# node.net
KiCad netlist of a schematic drawn in EAGLE
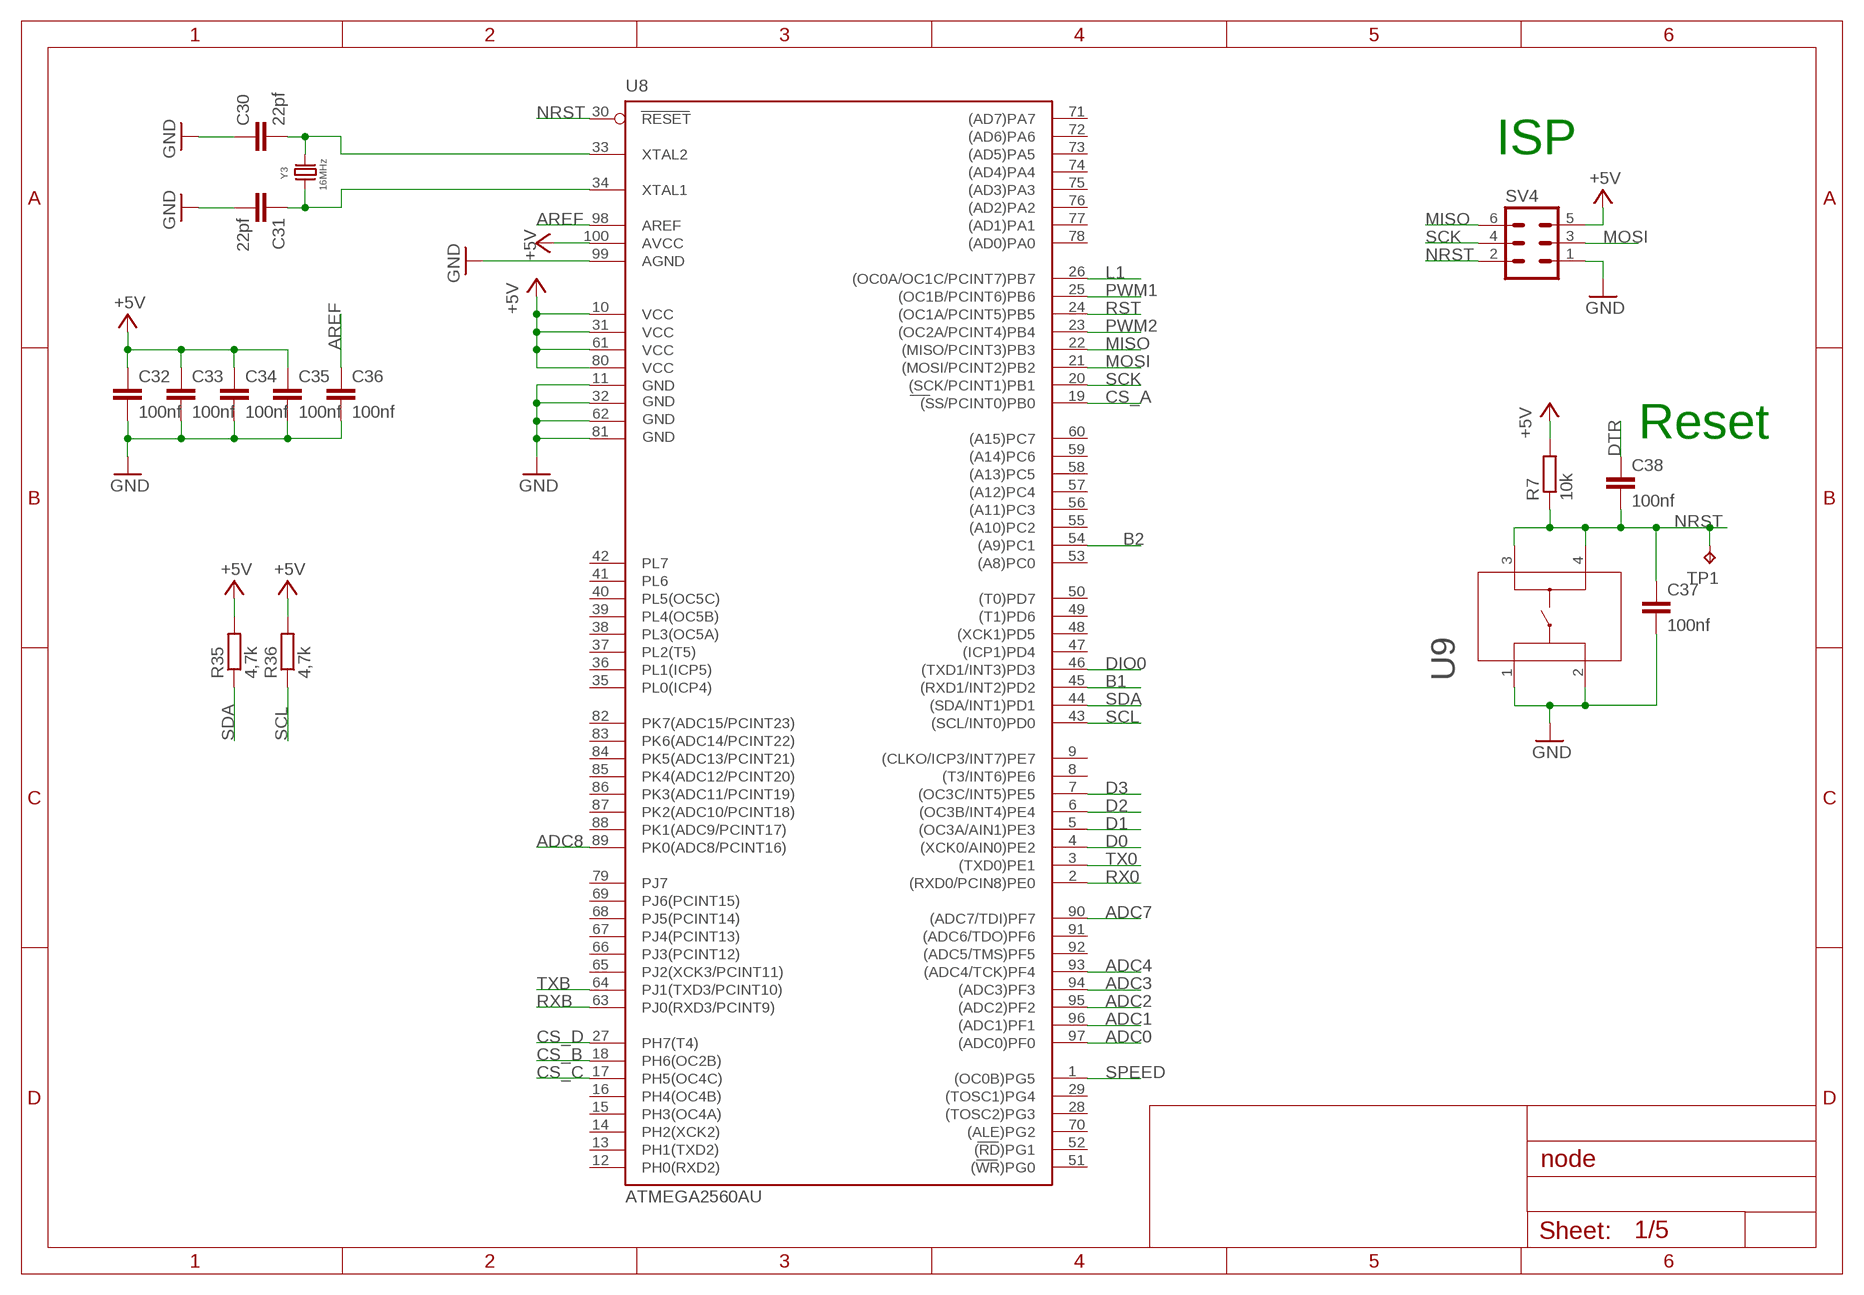
[diagram p0: schematic, sheet 1]
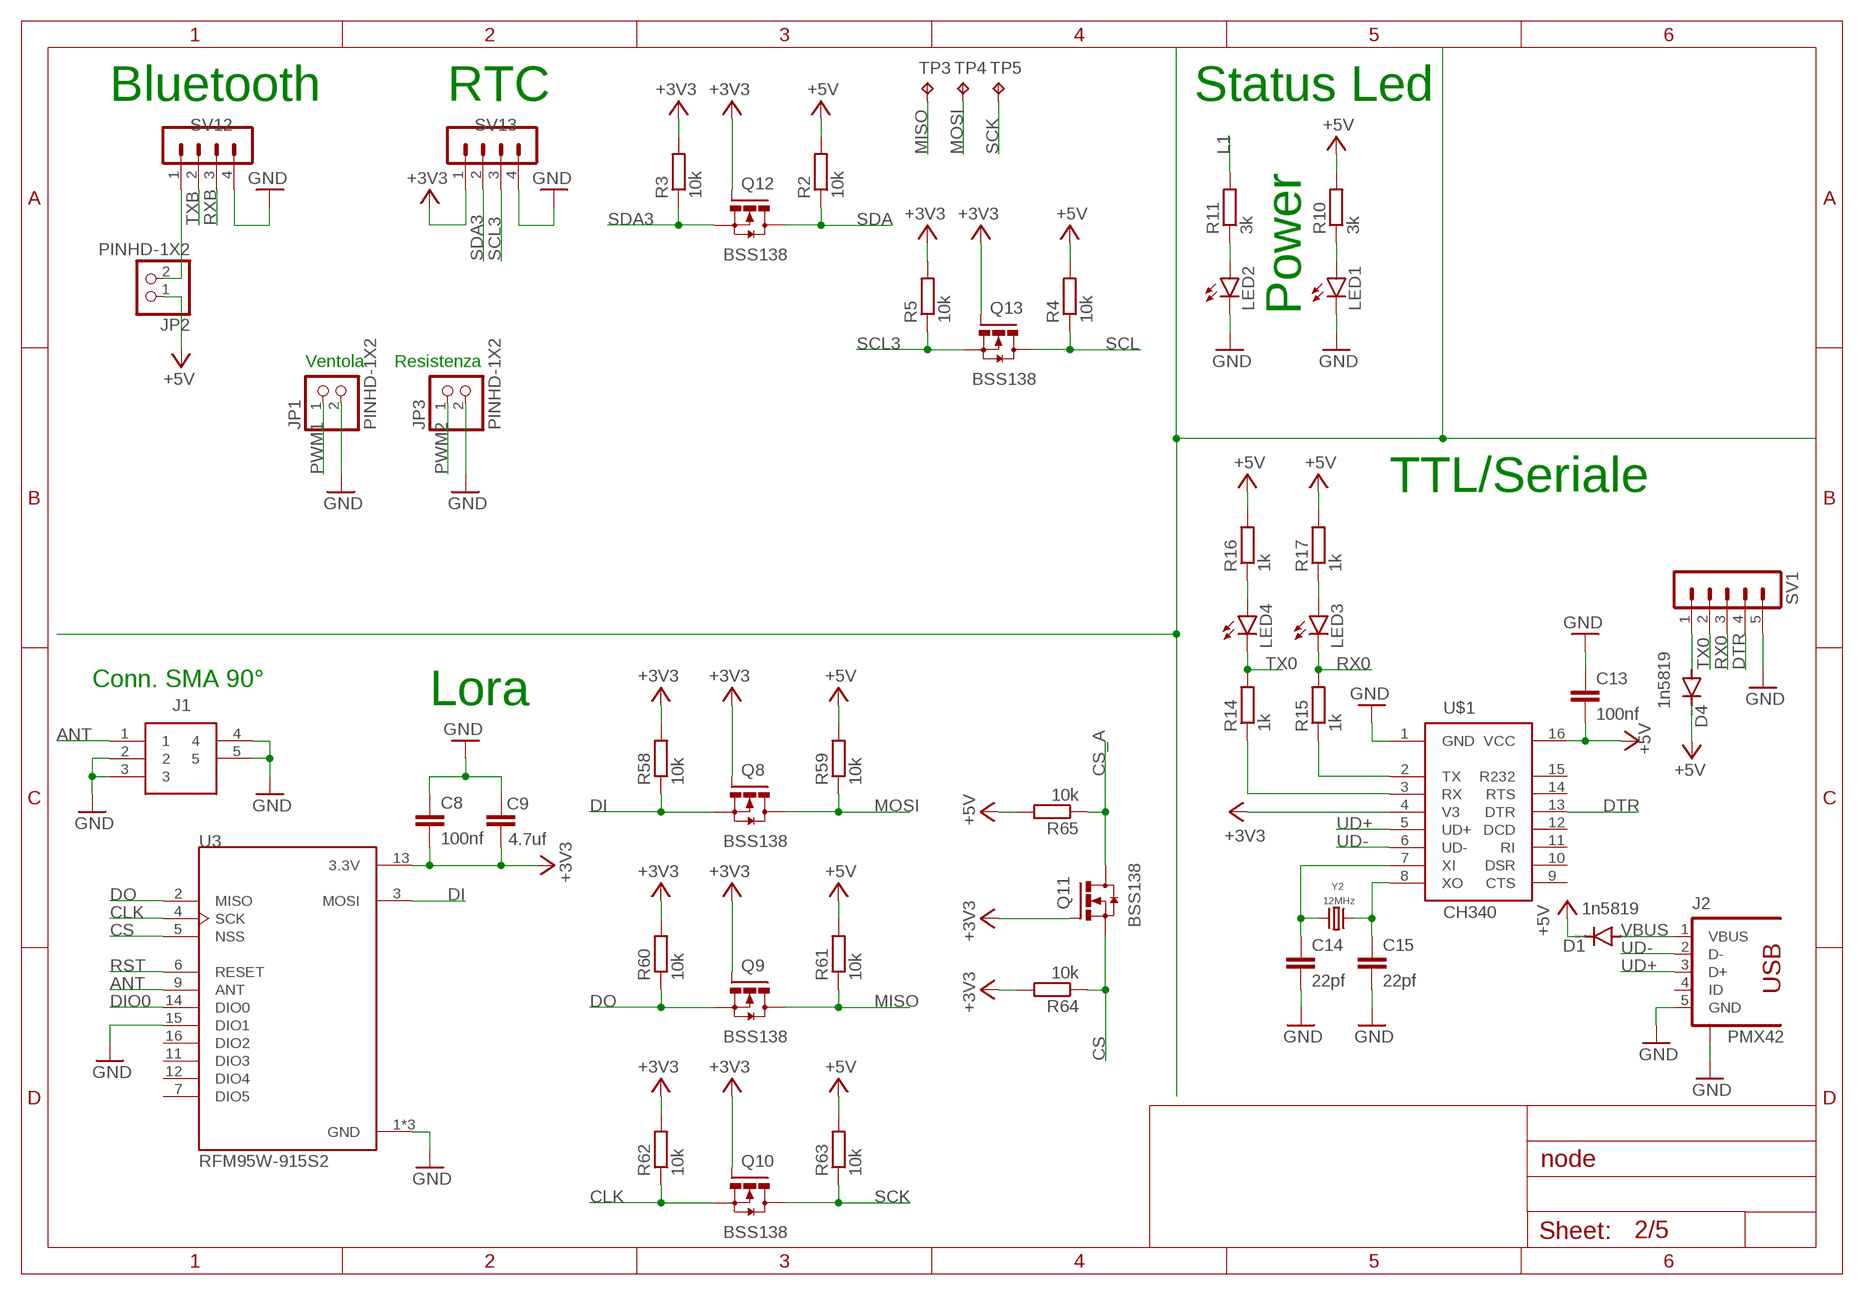
[diagram p1: schematic, sheet 2]
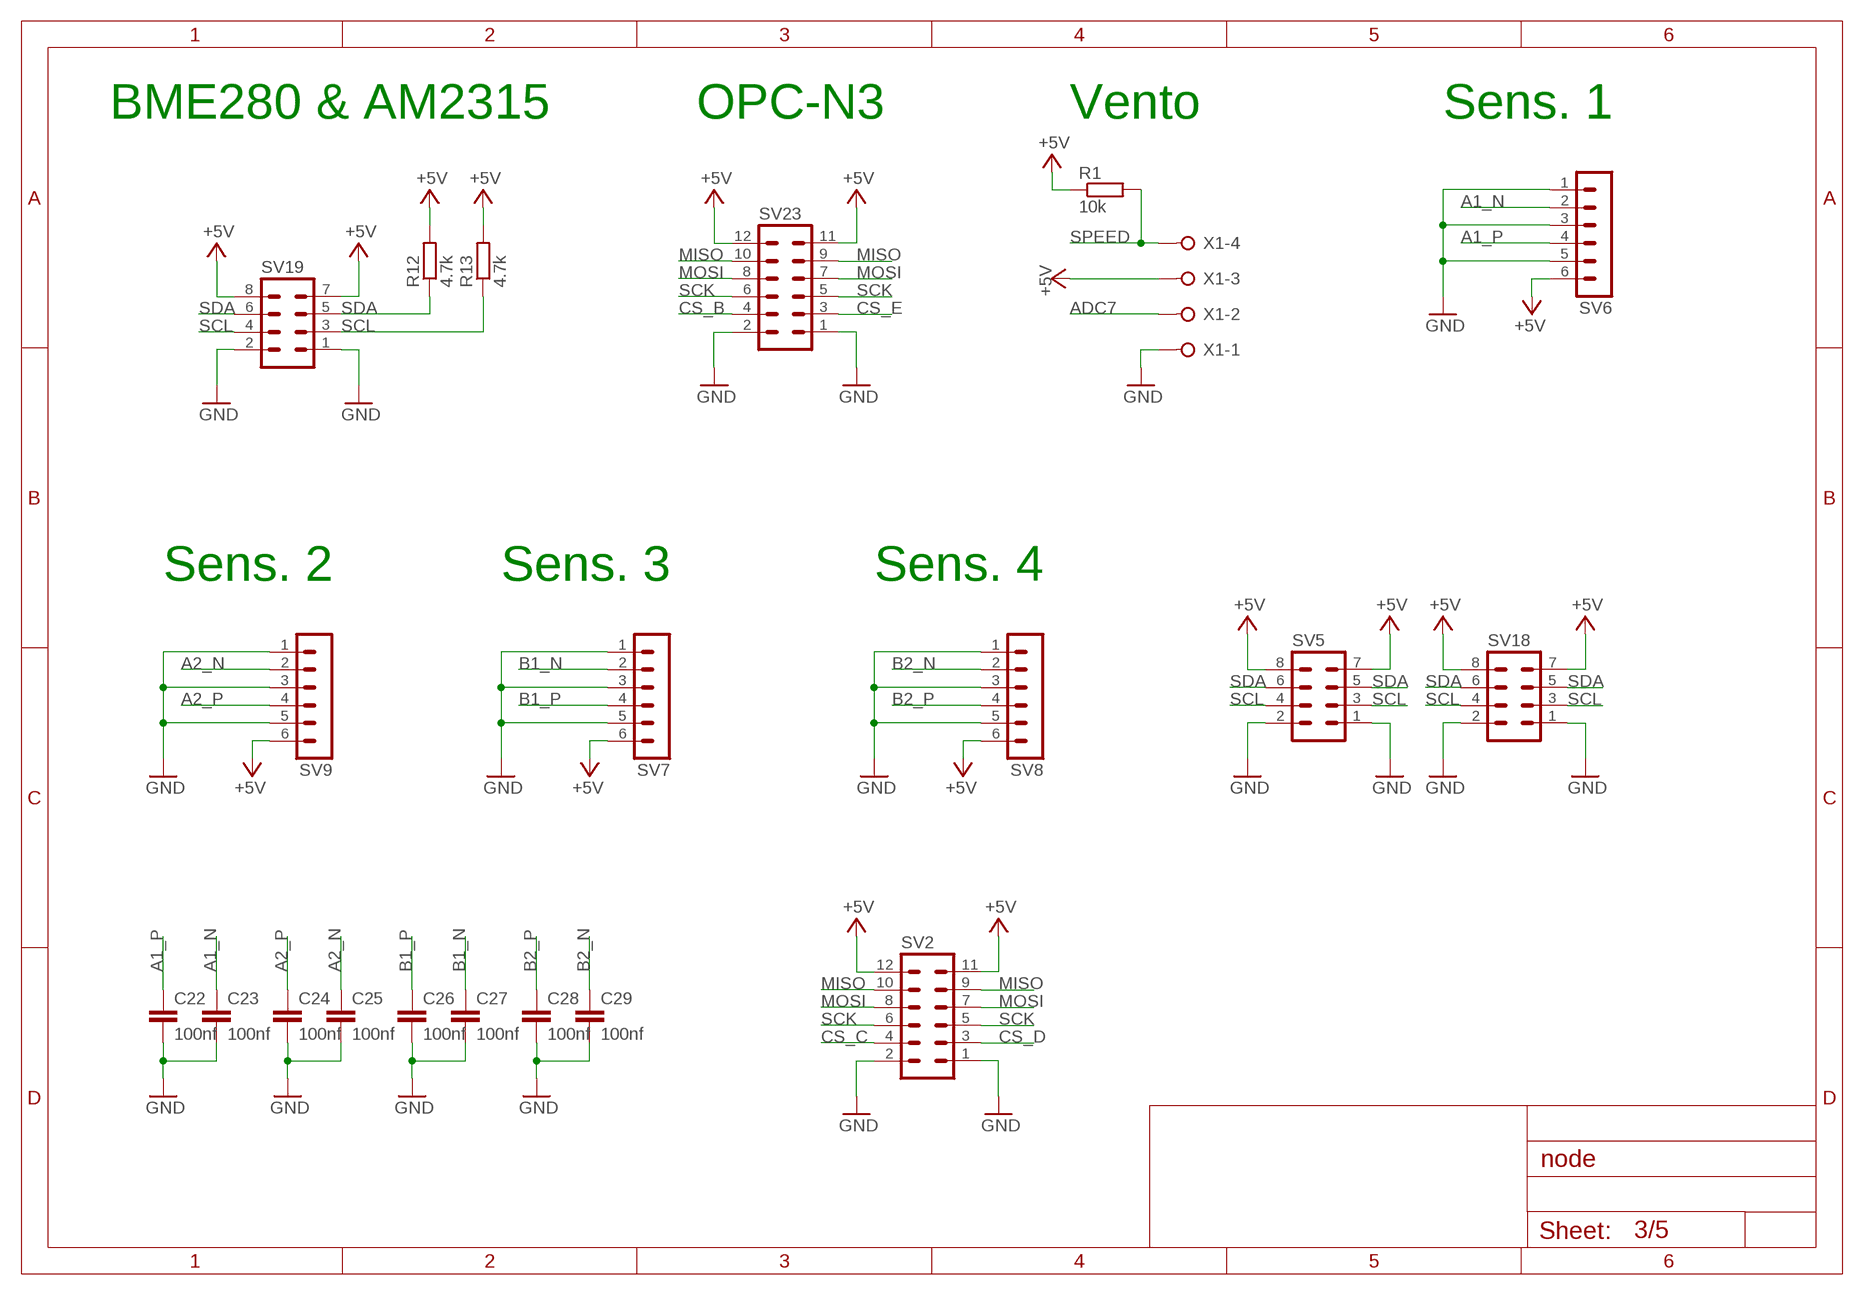
[diagram p2: schematic, sheet 3]
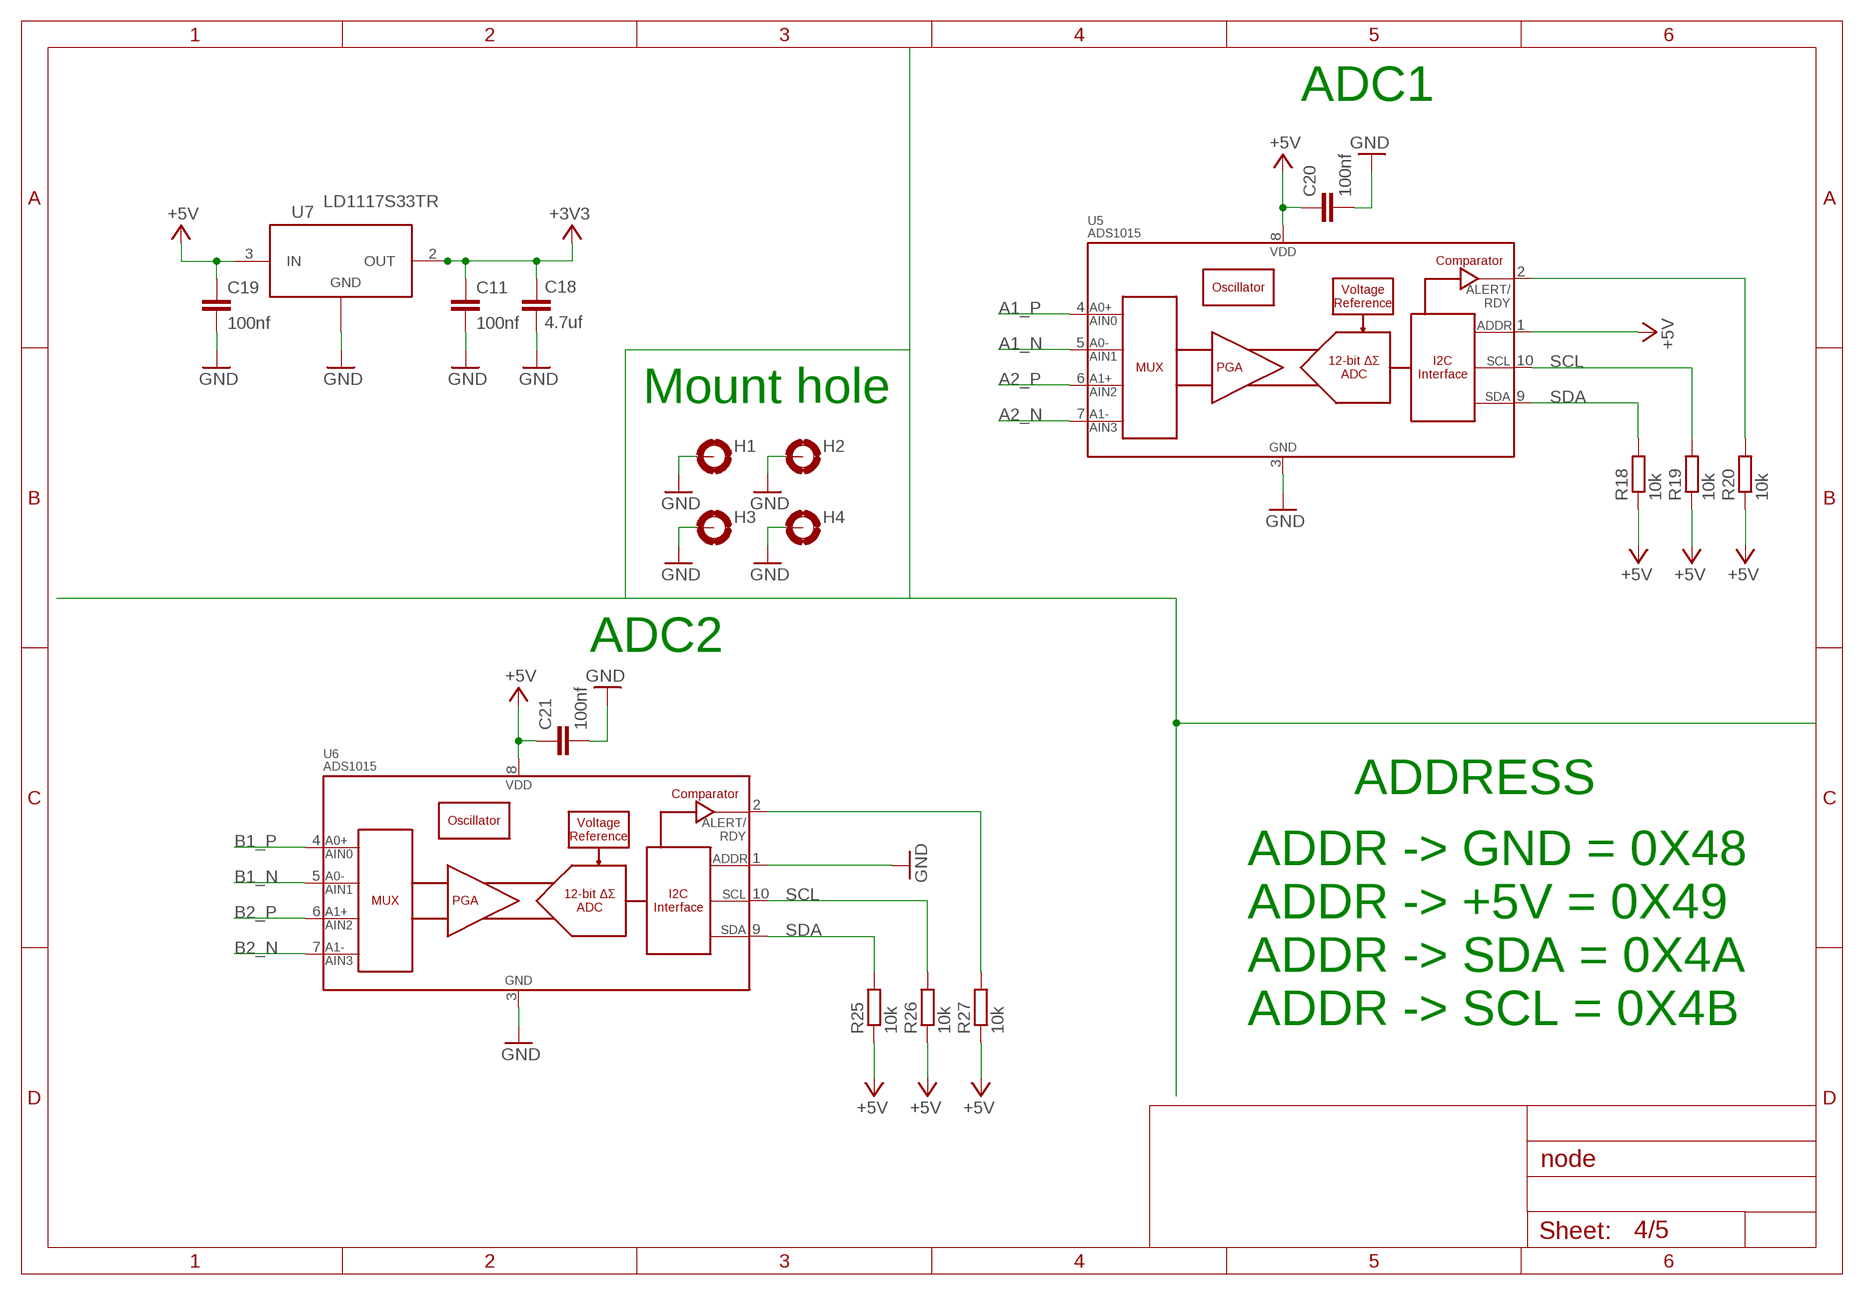
[diagram p3: schematic, sheet 4]
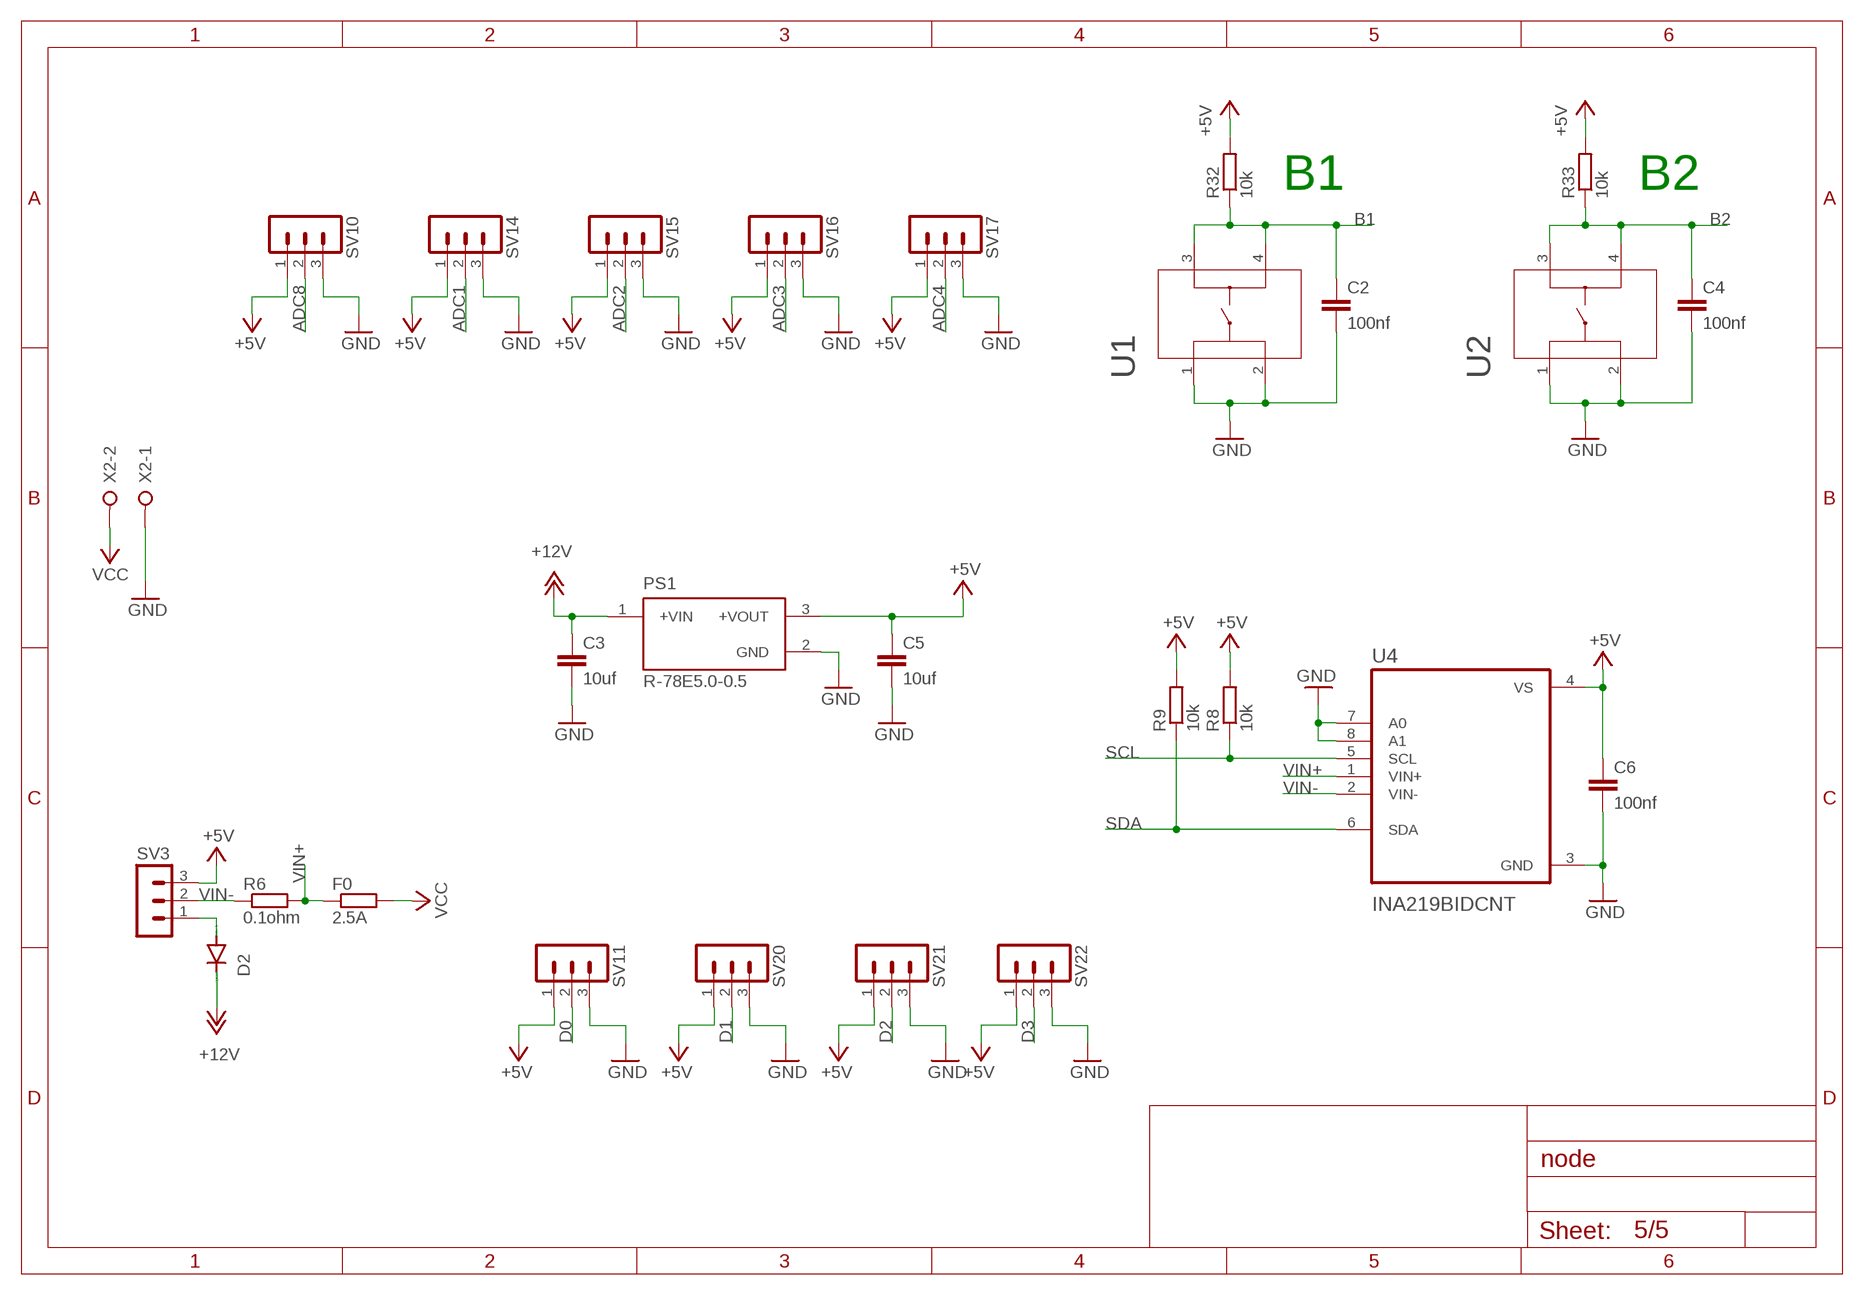
[diagram p4: schematic, sheet 5]

(export (version "E")
  (design (tool "Eeschema 10.0.6"))
  (components
    (comp (ref "C8")
      (value "100nf")
      (footprint "eagle-import:C0805")
      (libsource (lib "eagle-import") (part "C-EUC0805"))
    )
    (comp (ref "C9")
      (value "4.7uf")
      (footprint "eagle-import:C1206K")
      (libsource (lib "eagle-import") (part "C-EUC1206K"))
    )
    (comp (ref "C13")
      (value "100nf")
      (footprint "eagle-import:C0805")
      (libsource (lib "eagle-import") (part "C-EUC0805"))
    )
    (comp (ref "C14")
      (value "22pf")
      (footprint "eagle-import:C0603")
      (libsource (lib "eagle-import") (part "C-EUC0603"))
    )
    (comp (ref "C15")
      (value "22pf")
      (footprint "eagle-import:C0603")
      (libsource (lib "eagle-import") (part "C-EUC0603"))
    )
    (comp (ref "D1")
      (value "1n5819")
      (footprint "eagle-import:SOD123")
      (libsource (lib "eagle-import") (part "DIODE-SOD123"))
    )
    (comp (ref "D4")
      (value "1n5819")
      (footprint "eagle-import:SOD123")
      (libsource (lib "eagle-import") (part "DIODE-SOD123"))
    )
    (comp (ref "J1")
      (value "5-1814400-1")
      (footprint "eagle-import:518144001")
      (fields (field (name "MOUSER_PART_NUMBER") "571-5-1814400-1") (field (name "RS_PART_NUMBER") "6163400"))
      (libsource (lib "eagle-import") (part "5-1814400-1"))
    )
    (comp (ref "J2")
      (value "PMX42")
      (footprint "eagle-import:PMX42_56579-0576")
      (libsource (lib "eagle-import") (part "PMX42_56579-0576"))
    )
    (comp (ref "JP1")
      (value "PINHD-1X2")
      (footprint "eagle-import:1X02")
      (libsource (lib "eagle-import") (part "PINHD-1X2"))
    )
    (comp (ref "JP2")
      (value "PINHD-1X2")
      (footprint "eagle-import:1X02")
      (libsource (lib "eagle-import") (part "PINHD-1X2"))
    )
    (comp (ref "JP3")
      (value "PINHD-1X2")
      (footprint "eagle-import:1X02")
      (libsource (lib "eagle-import") (part "PINHD-1X2"))
    )
    (comp (ref "LED1")
      (value "LEDSML0805")
      (footprint "eagle-import:SML0805")
      (libsource (lib "eagle-import") (part "LEDSML0805"))
    )
    (comp (ref "LED2")
      (value "LEDSML0805")
      (footprint "eagle-import:SML0805")
      (libsource (lib "eagle-import") (part "LEDSML0805"))
    )
    (comp (ref "LED3")
      (value "LEDSML0805")
      (footprint "eagle-import:SML0805")
      (libsource (lib "eagle-import") (part "LEDSML0805"))
    )
    (comp (ref "LED4")
      (value "LEDSML0805")
      (footprint "eagle-import:SML0805")
      (libsource (lib "eagle-import") (part "LEDSML0805"))
    )
    (comp (ref "Q8")
      (value "BSS138")
      (footprint "eagle-import:SOT23-3")
      (fields
        (field (name "DIGIKEY_PART_NUMBER") "BSS138CT-ND")
        (field (name "MANUFACTURER") "ON Semiconductor")
        (field (name "CREATED_BY") "PCBLayout.com")
      )
      (libsource (lib "eagle-import") (part "BSS138"))
    )
    (comp (ref "Q9")
      (value "BSS138")
      (footprint "eagle-import:SOT23-3")
      (fields
        (field (name "DIGIKEY_PART_NUMBER") "BSS138CT-ND")
        (field (name "MANUFACTURER") "ON Semiconductor")
        (field (name "CREATED_BY") "PCBLayout.com")
      )
      (libsource (lib "eagle-import") (part "BSS138"))
    )
    (comp (ref "Q10")
      (value "BSS138")
      (footprint "eagle-import:SOT23-3")
      (fields
        (field (name "DIGIKEY_PART_NUMBER") "BSS138CT-ND")
        (field (name "MANUFACTURER") "ON Semiconductor")
        (field (name "CREATED_BY") "PCBLayout.com")
      )
      (libsource (lib "eagle-import") (part "BSS138"))
    )
    (comp (ref "Q11")
      (value "BSS138")
      (footprint "eagle-import:SOT23-3")
      (fields
        (field (name "DIGIKEY_PART_NUMBER") "BSS138CT-ND")
        (field (name "MANUFACTURER") "ON Semiconductor")
        (field (name "CREATED_BY") "PCBLayout.com")
      )
      (libsource (lib "eagle-import") (part "BSS138"))
    )
    (comp (ref "Q12")
      (value "BSS138")
      (footprint "eagle-import:SOT23-3")
      (fields
        (field (name "DIGIKEY_PART_NUMBER") "BSS138CT-ND")
        (field (name "MANUFACTURER") "ON Semiconductor")
        (field (name "CREATED_BY") "PCBLayout.com")
      )
      (libsource (lib "eagle-import") (part "BSS138"))
    )
    (comp (ref "Q13")
      (value "BSS138")
      (footprint "eagle-import:SOT23-3")
      (fields
        (field (name "DIGIKEY_PART_NUMBER") "BSS138CT-ND")
        (field (name "MANUFACTURER") "ON Semiconductor")
        (field (name "CREATED_BY") "PCBLayout.com")
      )
      (libsource (lib "eagle-import") (part "BSS138"))
    )
    (comp (ref "R2")
      (value "10k")
      (footprint "eagle-import:R0805")
      (libsource (lib "eagle-import") (part "R-EU_R0805"))
    )
    (comp (ref "R3")
      (value "10k")
      (footprint "eagle-import:R0805")
      (libsource (lib "eagle-import") (part "R-EU_R0805"))
    )
    (comp (ref "R4")
      (value "10k")
      (footprint "eagle-import:R0805")
      (libsource (lib "eagle-import") (part "R-EU_R0805"))
    )
    (comp (ref "R5")
      (value "10k")
      (footprint "eagle-import:R0805")
      (libsource (lib "eagle-import") (part "R-EU_R0805"))
    )
    (comp (ref "R10")
      (value "3k")
      (footprint "eagle-import:R0805")
      (libsource (lib "eagle-import") (part "R-EU_R0805"))
    )
    (comp (ref "R11")
      (value "3k")
      (footprint "eagle-import:R0805")
      (libsource (lib "eagle-import") (part "R-EU_R0805"))
    )
    (comp (ref "R14")
      (value "1k")
      (footprint "eagle-import:R0805")
      (libsource (lib "eagle-import") (part "R-EU_R0805"))
    )
    (comp (ref "R15")
      (value "1k")
      (footprint "eagle-import:R0805")
      (libsource (lib "eagle-import") (part "R-EU_R0805"))
    )
    (comp (ref "R16")
      (value "1k")
      (footprint "eagle-import:R0805")
      (libsource (lib "eagle-import") (part "R-EU_R0805"))
    )
    (comp (ref "R17")
      (value "1k")
      (footprint "eagle-import:R0805")
      (libsource (lib "eagle-import") (part "R-EU_R0805"))
    )
    (comp (ref "R58")
      (value "10k")
      (footprint "eagle-import:R0805")
      (libsource (lib "eagle-import") (part "R-EU_R0805"))
    )
    (comp (ref "R59")
      (value "10k")
      (footprint "eagle-import:R0805")
      (libsource (lib "eagle-import") (part "R-EU_R0805"))
    )
    (comp (ref "R60")
      (value "10k")
      (footprint "eagle-import:R0805")
      (libsource (lib "eagle-import") (part "R-EU_R0805"))
    )
    (comp (ref "R61")
      (value "10k")
      (footprint "eagle-import:R0805")
      (libsource (lib "eagle-import") (part "R-EU_R0805"))
    )
    (comp (ref "R62")
      (value "10k")
      (footprint "eagle-import:R0805")
      (libsource (lib "eagle-import") (part "R-EU_R0805"))
    )
    (comp (ref "R63")
      (value "10k")
      (footprint "eagle-import:R0805")
      (libsource (lib "eagle-import") (part "R-EU_R0805"))
    )
    (comp (ref "R64")
      (value "10k")
      (footprint "eagle-import:R0805")
      (libsource (lib "eagle-import") (part "R-EU_R0805"))
    )
    (comp (ref "R65")
      (value "10k")
      (footprint "eagle-import:R0805")
      (libsource (lib "eagle-import") (part "R-EU_R0805"))
    )
    (comp (ref "SV1")
      (value "MA05-1")
      (footprint "eagle-import:MA05-1")
      (libsource (lib "eagle-import") (part "MA05-1"))
    )
    (comp (ref "SV12")
      (value "MA04-1")
      (footprint "eagle-import:MA04-1")
      (libsource (lib "eagle-import") (part "MA04-1"))
    )
    (comp (ref "SV13")
      (value "MA04-1")
      (footprint "eagle-import:MA04-1")
      (libsource (lib "eagle-import") (part "MA04-1"))
    )
    (comp (ref "TP3")
      (value "TPTP13R")
      (footprint "eagle-import:TP13R")
      (libsource (lib "eagle-import") (part "TPTP13R"))
    )
    (comp (ref "TP4")
      (value "TPTP13R")
      (footprint "eagle-import:TP13R")
      (libsource (lib "eagle-import") (part "TPTP13R"))
    )
    (comp (ref "TP5")
      (value "TPTP13R")
      (footprint "eagle-import:TP13R")
      (libsource (lib "eagle-import") (part "TPTP13R"))
    )
    (comp (ref "U$1")
      (value "CH340")
      (footprint "eagle-import:SOIC16")
      (fields (field (name "MF") "Eaton"))
      (libsource (lib "eagle-import") (part "CH340"))
    )
    (comp (ref "U3")
      (value "RFM95W-915S2")
      (footprint "eagle-import:XCVR_RFM95W-915S2")
      (fields (field (name "MF") "RF Solutions"))
      (libsource (lib "eagle-import") (part "RFM95W-915S2"))
    )
    (comp (ref "Y2")
      (value "12MHz")
      (footprint "eagle-import:WE-XTAL_HC49_4H")
      (fields (field (name "TOLERANCE") "±30ppm"))
      (libsource (lib "eagle-import") (part "WE-XTAL_HC49/4H_830003063B"))
    )
    (comp (ref "C2")
      (value "100nf")
      (footprint "eagle-import:C0805")
      (libsource (lib "eagle-import") (part "C-EUC0805"))
    )
    (comp (ref "C3")
      (value "10uf")
      (footprint "eagle-import:C1206")
      (libsource (lib "eagle-import") (part "C-EUC1206"))
    )
    (comp (ref "C4")
      (value "100nf")
      (footprint "eagle-import:C0805")
      (libsource (lib "eagle-import") (part "C-EUC0805"))
    )
    (comp (ref "C5")
      (value "10uf")
      (footprint "eagle-import:C1206")
      (libsource (lib "eagle-import") (part "C-EUC1206"))
    )
    (comp (ref "C6")
      (value "100nf")
      (footprint "eagle-import:C0805")
      (libsource (lib "eagle-import") (part "C-EUC0805"))
    )
    (comp (ref "D2")
      (value "DIODE-SOD123")
      (footprint "eagle-import:SOD123")
      (libsource (lib "eagle-import") (part "DIODE-SOD123"))
    )
    (comp (ref "F0")
      (value "2.5A")
      (footprint "eagle-import:R0805")
      (libsource (lib "eagle-import") (part "R-EU_R0805"))
    )
    (comp (ref "PS1")
      (value "R-78E5.0-0.5")
      (footprint "eagle-import:CONV_R-78E5.0-0.5")
      (fields (field (name "MF") "Recom Power"))
      (libsource (lib "eagle-import") (part "R-78E5.0-0.5"))
    )
    (comp (ref "R6")
      (value "0.1ohm")
      (footprint "eagle-import:R2512")
      (libsource (lib "eagle-import") (part "R-EU_R2512"))
    )
    (comp (ref "R8")
      (value "10k")
      (footprint "eagle-import:R0805")
      (libsource (lib "eagle-import") (part "R-EU_R0805"))
    )
    (comp (ref "R9")
      (value "10k")
      (footprint "eagle-import:R0805")
      (libsource (lib "eagle-import") (part "R-EU_R0805"))
    )
    (comp (ref "R32")
      (value "10k")
      (footprint "eagle-import:R0805")
      (libsource (lib "eagle-import") (part "R-EU_R0805"))
    )
    (comp (ref "R33")
      (value "10k")
      (footprint "eagle-import:R0805")
      (libsource (lib "eagle-import") (part "R-EU_R0805"))
    )
    (comp (ref "SV3")
      (value "MA03-1")
      (footprint "eagle-import:MA03-1")
      (libsource (lib "eagle-import") (part "MA03-1"))
    )
    (comp (ref "SV10")
      (value "MA03-1")
      (footprint "eagle-import:MA03-1")
      (libsource (lib "eagle-import") (part "MA03-1"))
    )
    (comp (ref "SV11")
      (value "MA03-1")
      (footprint "eagle-import:MA03-1")
      (libsource (lib "eagle-import") (part "MA03-1"))
    )
    (comp (ref "SV14")
      (value "MA03-1")
      (footprint "eagle-import:MA03-1")
      (libsource (lib "eagle-import") (part "MA03-1"))
    )
    (comp (ref "SV15")
      (value "MA03-1")
      (footprint "eagle-import:MA03-1")
      (libsource (lib "eagle-import") (part "MA03-1"))
    )
    (comp (ref "SV16")
      (value "MA03-1")
      (footprint "eagle-import:MA03-1")
      (libsource (lib "eagle-import") (part "MA03-1"))
    )
    (comp (ref "SV17")
      (value "MA03-1")
      (footprint "eagle-import:MA03-1")
      (libsource (lib "eagle-import") (part "MA03-1"))
    )
    (comp (ref "SV20")
      (value "MA03-1")
      (footprint "eagle-import:MA03-1")
      (libsource (lib "eagle-import") (part "MA03-1"))
    )
    (comp (ref "SV21")
      (value "MA03-1")
      (footprint "eagle-import:MA03-1")
      (libsource (lib "eagle-import") (part "MA03-1"))
    )
    (comp (ref "SV22")
      (value "MA03-1")
      (footprint "eagle-import:MA03-1")
      (libsource (lib "eagle-import") (part "MA03-1"))
    )
    (comp (ref "U1")
      (value "1-1825910-0")
      (footprint "eagle-import:SWITCH_1-1825910-0")
      (fields (field (name "COPYRIGHT") "Copyright (C) 2016 Accelerated Designs. All rights reserved"))
      (libsource (lib "eagle-import") (part "1-1825910-0"))
    )
    (comp (ref "U2")
      (value "1-1825910-0")
      (footprint "eagle-import:SWITCH_1-1825910-0")
      (fields (field (name "COPYRIGHT") "Copyright (C) 2016 Accelerated Designs. All rights reserved"))
      (libsource (lib "eagle-import") (part "1-1825910-0"))
    )
    (comp (ref "U4")
      (value "INA219BIDCNT")
      (footprint "eagle-import:SOT65P280X145-8N")
      (fields (field (name "MF") "Texas Instruments"))
      (libsource (lib "eagle-import") (part "INA219BIDCNT"))
    )
    (comp (ref "X2")
      (value "W237-02P")
      (footprint "eagle-import:W237-132")
      (libsource (lib "eagle-import") (part "W237-02P"))
    )
    (comp (ref "C22")
      (value "100nf")
      (footprint "eagle-import:C0805")
      (libsource (lib "eagle-import") (part "C-EUC0805"))
    )
    (comp (ref "C23")
      (value "100nf")
      (footprint "eagle-import:C0805")
      (libsource (lib "eagle-import") (part "C-EUC0805"))
    )
    (comp (ref "C24")
      (value "100nf")
      (footprint "eagle-import:C0805")
      (libsource (lib "eagle-import") (part "C-EUC0805"))
    )
    (comp (ref "C25")
      (value "100nf")
      (footprint "eagle-import:C0805")
      (libsource (lib "eagle-import") (part "C-EUC0805"))
    )
    (comp (ref "C26")
      (value "100nf")
      (footprint "eagle-import:C0805")
      (libsource (lib "eagle-import") (part "C-EUC0805"))
    )
    (comp (ref "C27")
      (value "100nf")
      (footprint "eagle-import:C0805")
      (libsource (lib "eagle-import") (part "C-EUC0805"))
    )
    (comp (ref "C28")
      (value "100nf")
      (footprint "eagle-import:C0805")
      (libsource (lib "eagle-import") (part "C-EUC0805"))
    )
    (comp (ref "C29")
      (value "100nf")
      (footprint "eagle-import:C0805")
      (libsource (lib "eagle-import") (part "C-EUC0805"))
    )
    (comp (ref "R1")
      (value "10k")
      (footprint "eagle-import:R0805")
      (libsource (lib "eagle-import") (part "R-EU_R0805"))
    )
    (comp (ref "R12")
      (value "4.7k")
      (footprint "eagle-import:R0603")
      (libsource (lib "eagle-import") (part "R-EU_R0603"))
    )
    (comp (ref "R13")
      (value "4.7k")
      (footprint "eagle-import:R0603")
      (libsource (lib "eagle-import") (part "R-EU_R0603"))
    )
    (comp (ref "SV2")
      (value "MA06-2")
      (footprint "eagle-import:MA06-2")
      (libsource (lib "eagle-import") (part "MA06-2"))
    )
    (comp (ref "SV5")
      (value "MA04-2")
      (footprint "eagle-import:MA04-2")
      (libsource (lib "eagle-import") (part "MA04-2"))
    )
    (comp (ref "SV6")
      (value "MA06-1")
      (footprint "eagle-import:MA06-1")
      (libsource (lib "eagle-import") (part "MA06-1"))
    )
    (comp (ref "SV7")
      (value "MA06-1")
      (footprint "eagle-import:MA06-1")
      (libsource (lib "eagle-import") (part "MA06-1"))
    )
    (comp (ref "SV8")
      (value "MA06-1")
      (footprint "eagle-import:MA06-1")
      (libsource (lib "eagle-import") (part "MA06-1"))
    )
    (comp (ref "SV9")
      (value "MA06-1")
      (footprint "eagle-import:MA06-1")
      (libsource (lib "eagle-import") (part "MA06-1"))
    )
    (comp (ref "SV18")
      (value "MA04-2")
      (footprint "eagle-import:MA04-2")
      (libsource (lib "eagle-import") (part "MA04-2"))
    )
    (comp (ref "SV19")
      (value "MA04-2")
      (footprint "eagle-import:MA04-2")
      (libsource (lib "eagle-import") (part "MA04-2"))
    )
    (comp (ref "SV23")
      (value "MA06-2")
      (footprint "eagle-import:MA06-2")
      (libsource (lib "eagle-import") (part "MA06-2"))
    )
    (comp (ref "X1")
      (value "W237-04P")
      (footprint "eagle-import:W237-4P")
      (libsource (lib "eagle-import") (part "W237-04P"))
    )
    (comp (ref "C11")
      (value "100nf")
      (footprint "eagle-import:C0805")
      (libsource (lib "eagle-import") (part "C-EUC0805"))
    )
    (comp (ref "C18")
      (value "4.7uf")
      (footprint "eagle-import:C1206K")
      (libsource (lib "eagle-import") (part "C-EUC1206K"))
    )
    (comp (ref "C19")
      (value "100nf")
      (footprint "eagle-import:C0805")
      (libsource (lib "eagle-import") (part "C-EUC0805"))
    )
    (comp (ref "C20")
      (value "100nf")
      (footprint "eagle-import:C0805")
      (libsource (lib "eagle-import") (part "C-EUC0805"))
    )
    (comp (ref "C21")
      (value "100nf")
      (footprint "eagle-import:C0805")
      (libsource (lib "eagle-import") (part "C-EUC0805"))
    )
    (comp (ref "H1")
      (value "MOUNT-PAD-ROUND3.2")
      (footprint "eagle-import:3,2-PAD")
      (libsource (lib "eagle-import") (part "MOUNT-PAD-ROUND3.2"))
    )
    (comp (ref "H2")
      (value "MOUNT-PAD-ROUND3.2")
      (footprint "eagle-import:3,2-PAD")
      (libsource (lib "eagle-import") (part "MOUNT-PAD-ROUND3.2"))
    )
    (comp (ref "H3")
      (value "MOUNT-PAD-ROUND3.2")
      (footprint "eagle-import:3,2-PAD")
      (libsource (lib "eagle-import") (part "MOUNT-PAD-ROUND3.2"))
    )
    (comp (ref "H4")
      (value "MOUNT-PAD-ROUND3.2")
      (footprint "eagle-import:3,2-PAD")
      (libsource (lib "eagle-import") (part "MOUNT-PAD-ROUND3.2"))
    )
    (comp (ref "R18")
      (value "10k")
      (footprint "eagle-import:R0805")
      (libsource (lib "eagle-import") (part "R-EU_R0805"))
    )
    (comp (ref "R19")
      (value "10k")
      (footprint "eagle-import:R0805")
      (libsource (lib "eagle-import") (part "R-EU_R0805"))
    )
    (comp (ref "R20")
      (value "10k")
      (footprint "eagle-import:R0805")
      (libsource (lib "eagle-import") (part "R-EU_R0805"))
    )
    (comp (ref "R25")
      (value "10k")
      (footprint "eagle-import:R0805")
      (libsource (lib "eagle-import") (part "R-EU_R0805"))
    )
    (comp (ref "R26")
      (value "10k")
      (footprint "eagle-import:R0805")
      (libsource (lib "eagle-import") (part "R-EU_R0805"))
    )
    (comp (ref "R27")
      (value "10k")
      (footprint "eagle-import:R0805")
      (libsource (lib "eagle-import") (part "R-EU_R0805"))
    )
    (comp (ref "U5")
      (value "ADS1015")
      (footprint "eagle-import:MSOP10")
      (libsource (lib "eagle-import") (part "ADS1015"))
    )
    (comp (ref "U6")
      (value "ADS1015")
      (footprint "eagle-import:MSOP10")
      (libsource (lib "eagle-import") (part "ADS1015"))
    )
    (comp (ref "U7")
      (value "LD1117S33TR")
      (footprint "eagle-import:SOT-223")
      (fields
        (field (name "DIGIKEY_PART_NUMBER") "497-1242-2-ND")
        (field (name "MANUFACTURER") "STMicroelectronics")
        (field (name "CREATED_BY") "PCBLayout.com")
      )
      (libsource (lib "eagle-import") (part "LD1117S33TR"))
    )
    (comp (ref "C30")
      (value "22pf")
      (footprint "eagle-import:C0603")
      (libsource (lib "eagle-import") (part "C-EUC0603"))
    )
    (comp (ref "C31")
      (value "22pf")
      (footprint "eagle-import:C0603")
      (libsource (lib "eagle-import") (part "C-EUC0603"))
    )
    (comp (ref "C32")
      (value "100nf")
      (footprint "eagle-import:C0805")
      (libsource (lib "eagle-import") (part "C-EUC0805"))
    )
    (comp (ref "C33")
      (value "100nf")
      (footprint "eagle-import:C0805")
      (libsource (lib "eagle-import") (part "C-EUC0805"))
    )
    (comp (ref "C34")
      (value "100nf")
      (footprint "eagle-import:C0805")
      (libsource (lib "eagle-import") (part "C-EUC0805"))
    )
    (comp (ref "C35")
      (value "100nf")
      (footprint "eagle-import:C0805")
      (libsource (lib "eagle-import") (part "C-EUC0805"))
    )
    (comp (ref "C36")
      (value "100nf")
      (footprint "eagle-import:C0805")
      (libsource (lib "eagle-import") (part "C-EUC0805"))
    )
    (comp (ref "C37")
      (value "100nf")
      (footprint "eagle-import:C0805")
      (libsource (lib "eagle-import") (part "C-EUC0805"))
    )
    (comp (ref "C38")
      (value "100nf")
      (footprint "eagle-import:C0805")
      (libsource (lib "eagle-import") (part "C-EUC0805"))
    )
    (comp (ref "R7")
      (value "10k")
      (footprint "eagle-import:R0805")
      (libsource (lib "eagle-import") (part "R-EU_R0805"))
    )
    (comp (ref "R35")
      (value "4,7k")
      (footprint "eagle-import:R0603")
      (libsource (lib "eagle-import") (part "R-EU_R0603"))
    )
    (comp (ref "R36")
      (value "4,7k")
      (footprint "eagle-import:R0603")
      (libsource (lib "eagle-import") (part "R-EU_R0603"))
    )
    (comp (ref "SV4")
      (value "MA03-2")
      (footprint "eagle-import:MA03-2")
      (libsource (lib "eagle-import") (part "MA03-2"))
    )
    (comp (ref "TP1")
      (value "TPTP13R")
      (footprint "eagle-import:TP13R")
      (libsource (lib "eagle-import") (part "TPTP13R"))
    )
    (comp (ref "U8")
      (value "ATMEGA2560AU")
      (footprint "eagle-import:TQFP100")
      (libsource (lib "eagle-import") (part "ATMEGA2560AU"))
    )
    (comp (ref "U9")
      (value "1-1825910-0")
      (footprint "eagle-import:SWITCH_1-1825910-0")
      (fields (field (name "COPYRIGHT") "Copyright (C) 2016 Accelerated Designs. All rights reserved"))
      (libsource (lib "eagle-import") (part "1-1825910-0"))
    )
    (comp (ref "Y3")
      (value "16MHz")
      (footprint "eagle-import:WE-XTAL_HC49_4H")
      (fields (field (name "TOLERANCE") "±30ppm"))
      (libsource (lib "eagle-import") (part "WE-XTAL_HC49/4H_830003240B"))
    )
  )
  (nets
    (net (code "1") (name "+3V3") (class "Default")
      (node (ref "C11") (pin "1") (pinfunction "1_1") (pintype "passive"))
      (node (ref "C18") (pin "1") (pinfunction "1_1") (pintype "passive"))
      (node (ref "C8") (pin "2") (pinfunction "2_2") (pintype "passive"))
      (node (ref "C9") (pin "1") (pinfunction "1_1") (pintype "passive"))
      (node (ref "Q10") (pin "1") (pinfunction "G_1") (pintype "passive"))
      (node (ref "Q11") (pin "1") (pinfunction "G_1") (pintype "passive"))
      (node (ref "Q12") (pin "1") (pinfunction "G_1") (pintype "passive"))
      (node (ref "Q13") (pin "1") (pinfunction "G_1") (pintype "passive"))
      (node (ref "Q8") (pin "1") (pinfunction "G_1") (pintype "passive"))
      (node (ref "Q9") (pin "1") (pinfunction "G_1") (pintype "passive"))
      (node (ref "R3") (pin "2") (pinfunction "2_2") (pintype "passive"))
      (node (ref "R5") (pin "2") (pinfunction "2_2") (pintype "passive"))
      (node (ref "R58") (pin "2") (pinfunction "2_2") (pintype "passive"))
      (node (ref "R60") (pin "2") (pinfunction "2_2") (pintype "passive"))
      (node (ref "R62") (pin "2") (pinfunction "2_2") (pintype "passive"))
      (node (ref "R64") (pin "2") (pinfunction "2_2") (pintype "passive"))
      (node (ref "SV13") (pin "1") (pinfunction "1_1") (pintype "passive"))
      (node (ref "U$1") (pin "4") (pinfunction "V3_4") (pintype "power_in"))
      (node (ref "U3") (pin "13") (pinfunction "3.3V_13") (pintype "power_in"))
      (node (ref "U7") (pin "2") (pinfunction "OUT_2") (pintype "output"))
      (node (ref "U7") (pin "4") (pinfunction "4_4") (pintype "passive"))
    )
    (net (code "2") (name "+5V") (class "Default")
      (node (ref "C13") (pin "2") (pinfunction "2_2") (pintype "passive"))
      (node (ref "C19") (pin "1") (pinfunction "1_1") (pintype "passive"))
      (node (ref "C20") (pin "1") (pinfunction "1_1") (pintype "passive"))
      (node (ref "C21") (pin "1") (pinfunction "1_1") (pintype "passive"))
      (node (ref "C32") (pin "1") (pinfunction "1_1") (pintype "passive"))
      (node (ref "C33") (pin "1") (pinfunction "1_1") (pintype "passive"))
      (node (ref "C34") (pin "1") (pinfunction "1_1") (pintype "passive"))
      (node (ref "C35") (pin "1") (pinfunction "1_1") (pintype "passive"))
      (node (ref "C5") (pin "1") (pinfunction "1_1") (pintype "passive"))
      (node (ref "C6") (pin "1") (pinfunction "1_1") (pintype "passive"))
      (node (ref "D1") (pin "C") (pinfunction "C_C") (pintype "passive"))
      (node (ref "D4") (pin "C") (pinfunction "C_C") (pintype "passive"))
      (node (ref "JP2") (pin "1") (pinfunction "1_1") (pintype "passive"))
      (node (ref "PS1") (pin "3") (pinfunction "+VOUT_3") (pintype "output"))
      (node (ref "R1") (pin "1") (pinfunction "1_1") (pintype "passive"))
      (node (ref "R10") (pin "2") (pinfunction "2_2") (pintype "passive"))
      (node (ref "R12") (pin "2") (pinfunction "2_2") (pintype "passive"))
      (node (ref "R13") (pin "2") (pinfunction "2_2") (pintype "passive"))
      (node (ref "R16") (pin "2") (pinfunction "2_2") (pintype "passive"))
      (node (ref "R17") (pin "2") (pinfunction "2_2") (pintype "passive"))
      (node (ref "R18") (pin "1") (pinfunction "1_1") (pintype "passive"))
      (node (ref "R19") (pin "1") (pinfunction "1_1") (pintype "passive"))
      (node (ref "R2") (pin "2") (pinfunction "2_2") (pintype "passive"))
      (node (ref "R20") (pin "1") (pinfunction "1_1") (pintype "passive"))
      (node (ref "R25") (pin "1") (pinfunction "1_1") (pintype "passive"))
      (node (ref "R26") (pin "1") (pinfunction "1_1") (pintype "passive"))
      (node (ref "R27") (pin "1") (pinfunction "1_1") (pintype "passive"))
      (node (ref "R32") (pin "2") (pinfunction "2_2") (pintype "passive"))
      (node (ref "R33") (pin "2") (pinfunction "2_2") (pintype "passive"))
      (node (ref "R35") (pin "2") (pinfunction "2_2") (pintype "passive"))
      (node (ref "R36") (pin "2") (pinfunction "2_2") (pintype "passive"))
      (node (ref "R4") (pin "2") (pinfunction "2_2") (pintype "passive"))
      (node (ref "R59") (pin "2") (pinfunction "2_2") (pintype "passive"))
      (node (ref "R61") (pin "2") (pinfunction "2_2") (pintype "passive"))
      (node (ref "R63") (pin "2") (pinfunction "2_2") (pintype "passive"))
      (node (ref "R65") (pin "2") (pinfunction "2_2") (pintype "passive"))
      (node (ref "R7") (pin "2") (pinfunction "2_2") (pintype "passive"))
      (node (ref "R8") (pin "2") (pinfunction "2_2") (pintype "passive"))
      (node (ref "R9") (pin "2") (pinfunction "2_2") (pintype "passive"))
      (node (ref "SV10") (pin "1") (pinfunction "1_1") (pintype "passive"))
      (node (ref "SV11") (pin "1") (pinfunction "1_1") (pintype "passive"))
      (node (ref "SV14") (pin "1") (pinfunction "1_1") (pintype "passive"))
      (node (ref "SV15") (pin "1") (pinfunction "1_1") (pintype "passive"))
      (node (ref "SV16") (pin "1") (pinfunction "1_1") (pintype "passive"))
      (node (ref "SV17") (pin "1") (pinfunction "1_1") (pintype "passive"))
      (node (ref "SV18") (pin "7") (pinfunction "7_7") (pintype "passive"))
      (node (ref "SV18") (pin "8") (pinfunction "8_8") (pintype "passive"))
      (node (ref "SV19") (pin "7") (pinfunction "7_7") (pintype "passive"))
      (node (ref "SV19") (pin "8") (pinfunction "8_8") (pintype "passive"))
      (node (ref "SV2") (pin "11") (pinfunction "11_11") (pintype "passive"))
      (node (ref "SV2") (pin "12") (pinfunction "12_12") (pintype "passive"))
      (node (ref "SV20") (pin "1") (pinfunction "1_1") (pintype "passive"))
      (node (ref "SV21") (pin "1") (pinfunction "1_1") (pintype "passive"))
      (node (ref "SV22") (pin "1") (pinfunction "1_1") (pintype "passive"))
      (node (ref "SV23") (pin "11") (pinfunction "11_11") (pintype "passive"))
      (node (ref "SV23") (pin "12") (pinfunction "12_12") (pintype "passive"))
      (node (ref "SV3") (pin "3") (pinfunction "3_3") (pintype "passive"))
      (node (ref "SV4") (pin "5") (pinfunction "5_5") (pintype "passive"))
      (node (ref "SV5") (pin "7") (pinfunction "7_7") (pintype "passive"))
      (node (ref "SV5") (pin "8") (pinfunction "8_8") (pintype "passive"))
      (node (ref "SV6") (pin "6") (pinfunction "6_6") (pintype "passive"))
      (node (ref "SV7") (pin "6") (pinfunction "6_6") (pintype "passive"))
      (node (ref "SV8") (pin "6") (pinfunction "6_6") (pintype "passive"))
      (node (ref "SV9") (pin "6") (pinfunction "6_6") (pintype "passive"))
      (node (ref "U$1") (pin "16") (pinfunction "VCC_16") (pintype "power_in"))
      (node (ref "U4") (pin "4") (pinfunction "VS_4") (pintype "power_in"))
      (node (ref "U5") (pin "1") (pinfunction "ADDR_1") (pintype "bidirectional"))
      (node (ref "U5") (pin "8") (pinfunction "VDD_8") (pintype "bidirectional"))
      (node (ref "U6") (pin "8") (pinfunction "VDD_8") (pintype "bidirectional"))
      (node (ref "U7") (pin "3") (pinfunction "IN_3") (pintype "input"))
      (node (ref "U8") (pin "10") (pinfunction "VCC_10") (pintype "power_in"))
      (node (ref "U8") (pin "100") (pinfunction "AVCC_100") (pintype "power_in"))
      (node (ref "U8") (pin "31") (pinfunction "VCC1_31") (pintype "power_in"))
      (node (ref "U8") (pin "61") (pinfunction "VCC2_61") (pintype "power_in"))
      (node (ref "U8") (pin "80") (pinfunction "VCC3_80") (pintype "power_in"))
      (node (ref "X1") (pin "3") (pinfunction "KL_3") (pintype "passive"))
    )
    (net (code "3") (name "+12V") (class "Default")
      (node (ref "C3") (pin "1") (pinfunction "1_1") (pintype "passive"))
      (node (ref "D2") (pin "C") (pinfunction "C_C") (pintype "passive"))
      (node (ref "PS1") (pin "1") (pinfunction "+VIN_1") (pintype "input"))
    )
    (net (code "4") (name "A1_N") (class "Default")
      (node (ref "C23") (pin "1") (pinfunction "1_1") (pintype "passive"))
      (node (ref "SV6") (pin "2") (pinfunction "2_2") (pintype "passive"))
      (node (ref "U5") (pin "5") (pinfunction "AIN1_5") (pintype "bidirectional"))
    )
    (net (code "5") (name "A1_P") (class "Default")
      (node (ref "C22") (pin "1") (pinfunction "1_1") (pintype "passive"))
      (node (ref "SV6") (pin "4") (pinfunction "4_4") (pintype "passive"))
      (node (ref "U5") (pin "4") (pinfunction "AIN0_4") (pintype "bidirectional"))
    )
    (net (code "6") (name "A2_N") (class "Default")
      (node (ref "C25") (pin "1") (pinfunction "1_1") (pintype "passive"))
      (node (ref "SV9") (pin "2") (pinfunction "2_2") (pintype "passive"))
      (node (ref "U5") (pin "7") (pinfunction "AIN3_7") (pintype "bidirectional"))
    )
    (net (code "7") (name "A2_P") (class "Default")
      (node (ref "C24") (pin "1") (pinfunction "1_1") (pintype "passive"))
      (node (ref "SV9") (pin "4") (pinfunction "4_4") (pintype "passive"))
      (node (ref "U5") (pin "6") (pinfunction "AIN2_6") (pintype "bidirectional"))
    )
    (net (code "8") (name "ADC0") (class "Default")
      (node (ref "U8") (pin "97") (pinfunction "(ADC0)PF0_97") (pintype "bidirectional"))
    )
    (net (code "9") (name "ADC1") (class "Default")
      (node (ref "SV14") (pin "2") (pinfunction "2_2") (pintype "passive"))
      (node (ref "U8") (pin "96") (pinfunction "(ADC1)PF1_96") (pintype "bidirectional"))
    )
    (net (code "10") (name "ADC2") (class "Default")
      (node (ref "SV15") (pin "2") (pinfunction "2_2") (pintype "passive"))
      (node (ref "U8") (pin "95") (pinfunction "(ADC2)PF2_95") (pintype "bidirectional"))
    )
    (net (code "11") (name "ADC3") (class "Default")
      (node (ref "SV16") (pin "2") (pinfunction "2_2") (pintype "passive"))
      (node (ref "U8") (pin "94") (pinfunction "(ADC3)PF3_94") (pintype "bidirectional"))
    )
    (net (code "12") (name "ADC4") (class "Default")
      (node (ref "SV17") (pin "2") (pinfunction "2_2") (pintype "passive"))
      (node (ref "U8") (pin "93") (pinfunction "(ADC4/TCK)PF4_93") (pintype "bidirectional"))
    )
    (net (code "13") (name "ADC7") (class "Default")
      (node (ref "U8") (pin "90") (pinfunction "(ADC7/TDI)PF7_90") (pintype "bidirectional"))
      (node (ref "X1") (pin "2") (pinfunction "KL_2") (pintype "passive"))
    )
    (net (code "14") (name "ADC8") (class "Default")
      (node (ref "SV10") (pin "2") (pinfunction "2_2") (pintype "passive"))
      (node (ref "U8") (pin "89") (pinfunction "PK0(ADC8/PCINT16)_89") (pintype "bidirectional"))
    )
    (net (code "15") (name "ANT") (class "Default")
      (node (ref "J1") (pin "1") (pinfunction "1_1") (pintype "bidirectional"))
      (node (ref "U3") (pin "9") (pinfunction "ANT_9") (pintype "bidirectional"))
    )
    (net (code "16") (name "AREF") (class "Default")
      (node (ref "C36") (pin "1") (pinfunction "1_1") (pintype "passive"))
      (node (ref "U8") (pin "98") (pinfunction "AREF_98") (pintype "bidirectional"))
    )
    (net (code "17") (name "B1") (class "Default")
      (node (ref "C2") (pin "1") (pinfunction "1_1") (pintype "passive"))
      (node (ref "R32") (pin "1") (pinfunction "1_1") (pintype "passive"))
      (node (ref "U1") (pin "3") (pinfunction "3_3") (pintype "passive"))
      (node (ref "U1") (pin "4") (pinfunction "4_4") (pintype "passive"))
      (node (ref "U8") (pin "45") (pinfunction "(RXD1/INT2)PD2_45") (pintype "bidirectional"))
    )
    (net (code "18") (name "B1_N") (class "Default")
      (node (ref "C27") (pin "1") (pinfunction "1_1") (pintype "passive"))
      (node (ref "SV7") (pin "2") (pinfunction "2_2") (pintype "passive"))
      (node (ref "U6") (pin "5") (pinfunction "AIN1_5") (pintype "bidirectional"))
    )
    (net (code "19") (name "B1_P") (class "Default")
      (node (ref "C26") (pin "1") (pinfunction "1_1") (pintype "passive"))
      (node (ref "SV7") (pin "4") (pinfunction "4_4") (pintype "passive"))
      (node (ref "U6") (pin "4") (pinfunction "AIN0_4") (pintype "bidirectional"))
    )
    (net (code "20") (name "B2") (class "Default")
      (node (ref "C4") (pin "1") (pinfunction "1_1") (pintype "passive"))
      (node (ref "R33") (pin "1") (pinfunction "1_1") (pintype "passive"))
      (node (ref "U2") (pin "3") (pinfunction "3_3") (pintype "passive"))
      (node (ref "U2") (pin "4") (pinfunction "4_4") (pintype "passive"))
      (node (ref "U8") (pin "54") (pinfunction "(A9)PC1_54") (pintype "bidirectional"))
    )
    (net (code "21") (name "B2_N") (class "Default")
      (node (ref "C29") (pin "1") (pinfunction "1_1") (pintype "passive"))
      (node (ref "SV8") (pin "2") (pinfunction "2_2") (pintype "passive"))
      (node (ref "U6") (pin "7") (pinfunction "AIN3_7") (pintype "bidirectional"))
    )
    (net (code "22") (name "B2_P") (class "Default")
      (node (ref "C28") (pin "1") (pinfunction "1_1") (pintype "passive"))
      (node (ref "SV8") (pin "4") (pinfunction "4_4") (pintype "passive"))
      (node (ref "U6") (pin "6") (pinfunction "AIN2_6") (pintype "bidirectional"))
    )
    (net (code "23") (name "CLK") (class "Default")
      (node (ref "Q10") (pin "2") (pinfunction "S_2") (pintype "passive"))
      (node (ref "R62") (pin "1") (pinfunction "1_1") (pintype "passive"))
      (node (ref "U3") (pin "4") (pinfunction "SCK_4") (pintype "input"))
    )
    (net (code "24") (name "CS") (class "Default")
      (node (ref "Q11") (pin "2") (pinfunction "S_2") (pintype "passive"))
      (node (ref "R64") (pin "1") (pinfunction "1_1") (pintype "passive"))
      (node (ref "U3") (pin "5") (pinfunction "NSS_5") (pintype "input"))
    )
    (net (code "25") (name "CS_A") (class "Default")
      (node (ref "Q11") (pin "3") (pinfunction "D_3") (pintype "passive"))
      (node (ref "R65") (pin "1") (pinfunction "1_1") (pintype "passive"))
      (node (ref "U8") (pin "19") (pinfunction "(SS/PCINT0)PB0_19") (pintype "bidirectional"))
    )
    (net (code "26") (name "CS_B") (class "Default")
      (node (ref "SV23") (pin "4") (pinfunction "4_4") (pintype "passive"))
      (node (ref "U8") (pin "18") (pinfunction "PH6(OC2B)_18") (pintype "bidirectional"))
    )
    (net (code "27") (name "CS_C") (class "Default")
      (node (ref "SV2") (pin "4") (pinfunction "4_4") (pintype "passive"))
      (node (ref "U8") (pin "17") (pinfunction "PH5(OC4C)_17") (pintype "bidirectional"))
    )
    (net (code "28") (name "CS_D") (class "Default")
      (node (ref "SV2") (pin "3") (pinfunction "3_3") (pintype "passive"))
      (node (ref "U8") (pin "27") (pinfunction "PH7(T4)_27") (pintype "bidirectional"))
    )
    (net (code "29") (name "CS_E") (class "Default")
      (node (ref "SV23") (pin "3") (pinfunction "3_3") (pintype "passive"))
    )
    (net (code "30") (name "D0") (class "Default")
      (node (ref "SV11") (pin "2") (pinfunction "2_2") (pintype "passive"))
      (node (ref "U8") (pin "4") (pinfunction "(XCK0/AIN0)PE2_4") (pintype "bidirectional"))
    )
    (net (code "31") (name "D1") (class "Default")
      (node (ref "SV20") (pin "2") (pinfunction "2_2") (pintype "passive"))
      (node (ref "U8") (pin "5") (pinfunction "(OC3A/AIN1)PE3_5") (pintype "bidirectional"))
    )
    (net (code "32") (name "D2") (class "Default")
      (node (ref "SV21") (pin "2") (pinfunction "2_2") (pintype "passive"))
      (node (ref "U8") (pin "6") (pinfunction "(OC3B/INT4)PE4_6") (pintype "bidirectional"))
    )
    (net (code "33") (name "D3") (class "Default")
      (node (ref "SV22") (pin "2") (pinfunction "2_2") (pintype "passive"))
      (node (ref "U8") (pin "7") (pinfunction "(OC3C/INT5)PE5_7") (pintype "bidirectional"))
    )
    (net (code "34") (name "DI") (class "Default")
      (node (ref "Q8") (pin "2") (pinfunction "S_2") (pintype "passive"))
      (node (ref "R58") (pin "1") (pinfunction "1_1") (pintype "passive"))
      (node (ref "U3") (pin "3") (pinfunction "MOSI_3") (pintype "output"))
    )
    (net (code "35") (name "DIO0") (class "Default")
      (node (ref "U3") (pin "14") (pinfunction "DIO0_14") (pintype "bidirectional"))
      (node (ref "U8") (pin "46") (pinfunction "(TXD1/INT3)PD3_46") (pintype "bidirectional"))
    )
    (net (code "36") (name "DO") (class "Default")
      (node (ref "Q9") (pin "2") (pinfunction "S_2") (pintype "passive"))
      (node (ref "R60") (pin "1") (pinfunction "1_1") (pintype "passive"))
      (node (ref "U3") (pin "2") (pinfunction "MISO_2") (pintype "input"))
    )
    (net (code "37") (name "DTR") (class "Default")
      (node (ref "C38") (pin "1") (pinfunction "1_1") (pintype "passive"))
      (node (ref "SV1") (pin "4") (pinfunction "4_4") (pintype "passive"))
      (node (ref "U$1") (pin "13") (pinfunction "DTR_13") (pintype "bidirectional"))
    )
    (net (code "38") (name "GND") (class "Default")
      (node (ref "C11") (pin "2") (pinfunction "2_2") (pintype "passive"))
      (node (ref "C13") (pin "1") (pinfunction "1_1") (pintype "passive"))
      (node (ref "C14") (pin "2") (pinfunction "2_2") (pintype "passive"))
      (node (ref "C15") (pin "2") (pinfunction "2_2") (pintype "passive"))
      (node (ref "C18") (pin "2") (pinfunction "2_2") (pintype "passive"))
      (node (ref "C19") (pin "2") (pinfunction "2_2") (pintype "passive"))
      (node (ref "C2") (pin "2") (pinfunction "2_2") (pintype "passive"))
      (node (ref "C20") (pin "2") (pinfunction "2_2") (pintype "passive"))
      (node (ref "C21") (pin "2") (pinfunction "2_2") (pintype "passive"))
      (node (ref "C22") (pin "2") (pinfunction "2_2") (pintype "passive"))
      (node (ref "C23") (pin "2") (pinfunction "2_2") (pintype "passive"))
      (node (ref "C24") (pin "2") (pinfunction "2_2") (pintype "passive"))
      (node (ref "C25") (pin "2") (pinfunction "2_2") (pintype "passive"))
      (node (ref "C26") (pin "2") (pinfunction "2_2") (pintype "passive"))
      (node (ref "C27") (pin "2") (pinfunction "2_2") (pintype "passive"))
      (node (ref "C28") (pin "2") (pinfunction "2_2") (pintype "passive"))
      (node (ref "C29") (pin "2") (pinfunction "2_2") (pintype "passive"))
      (node (ref "C3") (pin "2") (pinfunction "2_2") (pintype "passive"))
      (node (ref "C30") (pin "1") (pinfunction "1_1") (pintype "passive"))
      (node (ref "C31") (pin "2") (pinfunction "2_2") (pintype "passive"))
      (node (ref "C32") (pin "2") (pinfunction "2_2") (pintype "passive"))
      (node (ref "C33") (pin "2") (pinfunction "2_2") (pintype "passive"))
      (node (ref "C34") (pin "2") (pinfunction "2_2") (pintype "passive"))
      (node (ref "C35") (pin "2") (pinfunction "2_2") (pintype "passive"))
      (node (ref "C36") (pin "2") (pinfunction "2_2") (pintype "passive"))
      (node (ref "C37") (pin "2") (pinfunction "2_2") (pintype "passive"))
      (node (ref "C4") (pin "2") (pinfunction "2_2") (pintype "passive"))
      (node (ref "C5") (pin "2") (pinfunction "2_2") (pintype "passive"))
      (node (ref "C6") (pin "2") (pinfunction "2_2") (pintype "passive"))
      (node (ref "C8") (pin "1") (pinfunction "1_1") (pintype "passive"))
      (node (ref "C9") (pin "2") (pinfunction "2_2") (pintype "passive"))
      (node (ref "H1") (pin "B3,2") (pinfunction "MOUNT_B3,2") (pintype "passive"))
      (node (ref "H2") (pin "B3,2") (pinfunction "MOUNT_B3,2") (pintype "passive"))
      (node (ref "H3") (pin "B3,2") (pinfunction "MOUNT_B3,2") (pintype "passive"))
      (node (ref "H4") (pin "B3,2") (pinfunction "MOUNT_B3,2") (pintype "passive"))
      (node (ref "J1") (pin "2") (pinfunction "2_2") (pintype "bidirectional"))
      (node (ref "J1") (pin "3") (pinfunction "3_3") (pintype "bidirectional"))
      (node (ref "J1") (pin "4") (pinfunction "4_4") (pintype "bidirectional"))
      (node (ref "J1") (pin "5") (pinfunction "5_5") (pintype "bidirectional"))
      (node (ref "J2") (pin "5") (pinfunction "GND_5") (pintype "passive"))
      (node (ref "J2") (pin "S1") (pinfunction "S_S1") (pintype "passive"))
      (node (ref "J2") (pin "S2") (pinfunction "S_S2") (pintype "passive"))
      (node (ref "J2") (pin "S3") (pinfunction "S_S3") (pintype "passive"))
      (node (ref "J2") (pin "S4") (pinfunction "S_S4") (pintype "passive"))
      (node (ref "JP1") (pin "2") (pinfunction "2_2") (pintype "passive"))
      (node (ref "JP3") (pin "2") (pinfunction "2_2") (pintype "passive"))
      (node (ref "LED1") (pin "C") (pinfunction "C_C") (pintype "passive"))
      (node (ref "LED2") (pin "C") (pinfunction "C_C") (pintype "passive"))
      (node (ref "PS1") (pin "2") (pinfunction "GND_2") (pintype "power_in"))
      (node (ref "SV1") (pin "5") (pinfunction "5_5") (pintype "passive"))
      (node (ref "SV10") (pin "3") (pinfunction "3_3") (pintype "passive"))
      (node (ref "SV11") (pin "3") (pinfunction "3_3") (pintype "passive"))
      (node (ref "SV12") (pin "4") (pinfunction "4_4") (pintype "passive"))
      (node (ref "SV13") (pin "4") (pinfunction "4_4") (pintype "passive"))
      (node (ref "SV14") (pin "3") (pinfunction "3_3") (pintype "passive"))
      (node (ref "SV15") (pin "3") (pinfunction "3_3") (pintype "passive"))
      (node (ref "SV16") (pin "3") (pinfunction "3_3") (pintype "passive"))
      (node (ref "SV17") (pin "3") (pinfunction "3_3") (pintype "passive"))
      (node (ref "SV18") (pin "1") (pinfunction "1_1") (pintype "passive"))
      (node (ref "SV18") (pin "2") (pinfunction "2_2") (pintype "passive"))
      (node (ref "SV19") (pin "1") (pinfunction "1_1") (pintype "passive"))
      (node (ref "SV19") (pin "2") (pinfunction "2_2") (pintype "passive"))
      (node (ref "SV2") (pin "1") (pinfunction "1_1") (pintype "passive"))
      (node (ref "SV2") (pin "2") (pinfunction "2_2") (pintype "passive"))
      (node (ref "SV20") (pin "3") (pinfunction "3_3") (pintype "passive"))
      (node (ref "SV21") (pin "3") (pinfunction "3_3") (pintype "passive"))
      (node (ref "SV22") (pin "3") (pinfunction "3_3") (pintype "passive"))
      (node (ref "SV23") (pin "1") (pinfunction "1_1") (pintype "passive"))
      (node (ref "SV23") (pin "2") (pinfunction "2_2") (pintype "passive"))
      (node (ref "SV4") (pin "1") (pinfunction "1_1") (pintype "passive"))
      (node (ref "SV5") (pin "1") (pinfunction "1_1") (pintype "passive"))
      (node (ref "SV5") (pin "2") (pinfunction "2_2") (pintype "passive"))
      (node (ref "SV6") (pin "1") (pinfunction "1_1") (pintype "passive"))
      (node (ref "SV6") (pin "3") (pinfunction "3_3") (pintype "passive"))
      (node (ref "SV6") (pin "5") (pinfunction "5_5") (pintype "passive"))
      (node (ref "SV7") (pin "1") (pinfunction "1_1") (pintype "passive"))
      (node (ref "SV7") (pin "3") (pinfunction "3_3") (pintype "passive"))
      (node (ref "SV7") (pin "5") (pinfunction "5_5") (pintype "passive"))
      (node (ref "SV8") (pin "1") (pinfunction "1_1") (pintype "passive"))
      (node (ref "SV8") (pin "3") (pinfunction "3_3") (pintype "passive"))
      (node (ref "SV8") (pin "5") (pinfunction "5_5") (pintype "passive"))
      (node (ref "SV9") (pin "1") (pinfunction "1_1") (pintype "passive"))
      (node (ref "SV9") (pin "3") (pinfunction "3_3") (pintype "passive"))
      (node (ref "SV9") (pin "5") (pinfunction "5_5") (pintype "passive"))
      (node (ref "U$1") (pin "1") (pinfunction "GND_1") (pintype "power_in"))
      (node (ref "U1") (pin "1") (pinfunction "1_1") (pintype "passive"))
      (node (ref "U1") (pin "2") (pinfunction "2_2") (pintype "passive"))
      (node (ref "U2") (pin "1") (pinfunction "1_1") (pintype "passive"))
      (node (ref "U2") (pin "2") (pinfunction "2_2") (pintype "passive"))
      (node (ref "U3") (pin "1") (pinfunction "GND_1") (pintype "power_in"))
      (node (ref "U3") (pin "10") (pinfunction "GND_10") (pintype "power_in"))
      (node (ref "U3") (pin "15") (pinfunction "DIO1_15") (pintype "bidirectional"))
      (node (ref "U3") (pin "8") (pinfunction "GND_8") (pintype "power_in"))
      (node (ref "U4") (pin "3") (pinfunction "GND_3") (pintype "power_in"))
      (node (ref "U4") (pin "7") (pinfunction "A0_7") (pintype "input"))
      (node (ref "U4") (pin "8") (pinfunction "A1_8") (pintype "input"))
      (node (ref "U5") (pin "3") (pinfunction "VSS_3") (pintype "bidirectional"))
      (node (ref "U6") (pin "1") (pinfunction "ADDR_1") (pintype "bidirectional"))
      (node (ref "U6") (pin "3") (pinfunction "VSS_3") (pintype "bidirectional"))
      (node (ref "U7") (pin "1") (pinfunction "ADJ/GND_1") (pintype "power_in"))
      (node (ref "U8") (pin "11") (pinfunction "GND_11") (pintype "power_in"))
      (node (ref "U8") (pin "32") (pinfunction "GND1_32") (pintype "power_in"))
      (node (ref "U8") (pin "62") (pinfunction "GND2_62") (pintype "power_in"))
      (node (ref "U8") (pin "81") (pinfunction "GND3_81") (pintype "power_in"))
      (node (ref "U8") (pin "99") (pinfunction "AGND_99") (pintype "power_in"))
      (node (ref "U9") (pin "1") (pinfunction "1_1") (pintype "passive"))
      (node (ref "U9") (pin "2") (pinfunction "2_2") (pintype "passive"))
      (node (ref "X1") (pin "1") (pinfunction "KL_1") (pintype "passive"))
      (node (ref "X2") (pin "1") (pinfunction "KL_1") (pintype "passive"))
    )
    (net (code "39") (name "L1") (class "Default")
      (node (ref "R11") (pin "2") (pinfunction "2_2") (pintype "passive"))
      (node (ref "U8") (pin "26") (pinfunction "(OC0A/OC1C/PCINT7)PB7_26") (pintype "bidirectional"))
    )
    (net (code "40") (name "MISO") (class "Default")
      (node (ref "Q9") (pin "3") (pinfunction "D_3") (pintype "passive"))
      (node (ref "R61") (pin "1") (pinfunction "1_1") (pintype "passive"))
      (node (ref "SV2") (pin "10") (pinfunction "10_10") (pintype "passive"))
      (node (ref "SV2") (pin "9") (pinfunction "9_9") (pintype "passive"))
      (node (ref "SV23") (pin "10") (pinfunction "10_10") (pintype "passive"))
      (node (ref "SV23") (pin "9") (pinfunction "9_9") (pintype "passive"))
      (node (ref "SV4") (pin "6") (pinfunction "6_6") (pintype "passive"))
      (node (ref "TP3") (pin "TP") (pinfunction "TP_TP") (pintype "input"))
      (node (ref "U8") (pin "22") (pinfunction "(MISO/PCINT3)PB3_22") (pintype "bidirectional"))
    )
    (net (code "41") (name "MOSI") (class "Default")
      (node (ref "Q8") (pin "3") (pinfunction "D_3") (pintype "passive"))
      (node (ref "R59") (pin "1") (pinfunction "1_1") (pintype "passive"))
      (node (ref "SV2") (pin "7") (pinfunction "7_7") (pintype "passive"))
      (node (ref "SV2") (pin "8") (pinfunction "8_8") (pintype "passive"))
      (node (ref "SV23") (pin "7") (pinfunction "7_7") (pintype "passive"))
      (node (ref "SV23") (pin "8") (pinfunction "8_8") (pintype "passive"))
      (node (ref "SV4") (pin "3") (pinfunction "3_3") (pintype "passive"))
      (node (ref "TP4") (pin "TP") (pinfunction "TP_TP") (pintype "input"))
      (node (ref "U8") (pin "21") (pinfunction "(MOSI/PCINT2)PB2_21") (pintype "bidirectional"))
    )
    (net (code "42") (name "NRST") (class "Default")
      (node (ref "C37") (pin "1") (pinfunction "1_1") (pintype "passive"))
      (node (ref "C38") (pin "2") (pinfunction "2_2") (pintype "passive"))
      (node (ref "R7") (pin "1") (pinfunction "1_1") (pintype "passive"))
      (node (ref "SV4") (pin "2") (pinfunction "2_2") (pintype "passive"))
      (node (ref "TP1") (pin "TP") (pinfunction "TP_TP") (pintype "input"))
      (node (ref "U8") (pin "30") (pinfunction "RESET_30") (pintype "input"))
      (node (ref "U9") (pin "3") (pinfunction "3_3") (pintype "passive"))
      (node (ref "U9") (pin "4") (pinfunction "4_4") (pintype "passive"))
    )
    (net (code "43") (name "Net-(D2-PadA)") (class "Default")
      (node (ref "D2") (pin "A") (pinfunction "A_A") (pintype "passive"))
      (node (ref "SV3") (pin "1") (pinfunction "1_1") (pintype "passive"))
    )
    (net (code "44") (name "Net-(D4-PadA)") (class "Default")
      (node (ref "D4") (pin "A") (pinfunction "A_A") (pintype "passive"))
      (node (ref "SV1") (pin "1") (pinfunction "1_1") (pintype "passive"))
    )
    (net (code "45") (name "Net-(JP2-Pad2)") (class "Default")
      (node (ref "JP2") (pin "2") (pinfunction "2_2") (pintype "passive"))
      (node (ref "SV12") (pin "1") (pinfunction "1_1") (pintype "passive"))
    )
    (net (code "46") (name "Net-(LED1-PadA)") (class "Default")
      (node (ref "LED1") (pin "A") (pinfunction "A_A") (pintype "passive"))
      (node (ref "R10") (pin "1") (pinfunction "1_1") (pintype "passive"))
    )
    (net (code "47") (name "Net-(LED2-PadA)") (class "Default")
      (node (ref "LED2") (pin "A") (pinfunction "A_A") (pintype "passive"))
      (node (ref "R11") (pin "1") (pinfunction "1_1") (pintype "passive"))
    )
    (net (code "48") (name "Net-(LED3-PadA)") (class "Default")
      (node (ref "LED3") (pin "A") (pinfunction "A_A") (pintype "passive"))
      (node (ref "R17") (pin "1") (pinfunction "1_1") (pintype "passive"))
    )
    (net (code "49") (name "Net-(LED4-PadA)") (class "Default")
      (node (ref "LED4") (pin "A") (pinfunction "A_A") (pintype "passive"))
      (node (ref "R16") (pin "1") (pinfunction "1_1") (pintype "passive"))
    )
    (net (code "50") (name "Net-(U$1-RX)") (class "Default")
      (node (ref "R14") (pin "1") (pinfunction "1_1") (pintype "passive"))
      (node (ref "U$1") (pin "3") (pinfunction "RX_3") (pintype "input"))
    )
    (net (code "51") (name "Net-(U$1-TX)") (class "Default")
      (node (ref "R15") (pin "1") (pinfunction "1_1") (pintype "passive"))
      (node (ref "U$1") (pin "2") (pinfunction "TX_2") (pintype "output"))
    )
    (net (code "52") (name "Net-(U$1-XI)") (class "Default")
      (node (ref "C14") (pin "1") (pinfunction "1_1") (pintype "passive"))
      (node (ref "U$1") (pin "7") (pinfunction "XI_7") (pintype "input"))
      (node (ref "Y2") (pin "2") (pinfunction "2_2") (pintype "passive"))
    )
    (net (code "53") (name "Net-(U$1-XO)") (class "Default")
      (node (ref "C15") (pin "1") (pinfunction "1_1") (pintype "passive"))
      (node (ref "U$1") (pin "8") (pinfunction "XO_8") (pintype "output"))
      (node (ref "Y2") (pin "1") (pinfunction "1_1") (pintype "passive"))
    )
    (net (code "54") (name "Net-(U5-ALERT{slash}RDY)") (class "Default")
      (node (ref "R20") (pin "2") (pinfunction "2_2") (pintype "passive"))
      (node (ref "U5") (pin "2") (pinfunction "ALERT/RDY_2") (pintype "bidirectional"))
    )
    (net (code "55") (name "Net-(U6-ALERT{slash}RDY)") (class "Default")
      (node (ref "R27") (pin "2") (pinfunction "2_2") (pintype "passive"))
      (node (ref "U6") (pin "2") (pinfunction "ALERT/RDY_2") (pintype "bidirectional"))
    )
    (net (code "56") (name "Net-(U8-XTAL1)") (class "Default")
      (node (ref "C31") (pin "1") (pinfunction "1_1") (pintype "passive"))
      (node (ref "U8") (pin "34") (pinfunction "XTAL1_34") (pintype "input"))
      (node (ref "Y3") (pin "1") (pinfunction "1_1") (pintype "passive"))
    )
    (net (code "57") (name "Net-(U8-XTAL2)") (class "Default")
      (node (ref "C30") (pin "2") (pinfunction "2_2") (pintype "passive"))
      (node (ref "U8") (pin "33") (pinfunction "XTAL2_33") (pintype "output"))
      (node (ref "Y3") (pin "2") (pinfunction "2_2") (pintype "passive"))
    )
    (net (code "58") (name "PWM1") (class "Default")
      (node (ref "JP1") (pin "1") (pinfunction "1_1") (pintype "passive"))
      (node (ref "U8") (pin "25") (pinfunction "(OC1B/PCINT6)PB6_25") (pintype "bidirectional"))
    )
    (net (code "59") (name "PWM2") (class "Default")
      (node (ref "JP3") (pin "1") (pinfunction "1_1") (pintype "passive"))
      (node (ref "U8") (pin "23") (pinfunction "(OC2A/PCINT4)PB4_23") (pintype "bidirectional"))
    )
    (net (code "60") (name "RST") (class "Default")
      (node (ref "U3") (pin "6") (pinfunction "RESET_6") (pintype "bidirectional"))
      (node (ref "U8") (pin "24") (pinfunction "(OC1A/PCINT5)PB5_24") (pintype "bidirectional"))
    )
    (net (code "61") (name "RX0") (class "Default")
      (node (ref "LED3") (pin "C") (pinfunction "C_C") (pintype "passive"))
      (node (ref "R15") (pin "2") (pinfunction "2_2") (pintype "passive"))
      (node (ref "SV1") (pin "3") (pinfunction "3_3") (pintype "passive"))
      (node (ref "U8") (pin "2") (pinfunction "(RXD0/PCIN8)PE0_2") (pintype "bidirectional"))
    )
    (net (code "62") (name "RXB") (class "Default")
      (node (ref "SV12") (pin "3") (pinfunction "3_3") (pintype "passive"))
      (node (ref "U8") (pin "63") (pinfunction "PJ0(RXD3/PCINT9)_63") (pintype "bidirectional"))
    )
    (net (code "63") (name "SCK") (class "Default")
      (node (ref "Q10") (pin "3") (pinfunction "D_3") (pintype "passive"))
      (node (ref "R63") (pin "1") (pinfunction "1_1") (pintype "passive"))
      (node (ref "SV2") (pin "5") (pinfunction "5_5") (pintype "passive"))
      (node (ref "SV2") (pin "6") (pinfunction "6_6") (pintype "passive"))
      (node (ref "SV23") (pin "5") (pinfunction "5_5") (pintype "passive"))
      (node (ref "SV23") (pin "6") (pinfunction "6_6") (pintype "passive"))
      (node (ref "SV4") (pin "4") (pinfunction "4_4") (pintype "passive"))
      (node (ref "TP5") (pin "TP") (pinfunction "TP_TP") (pintype "input"))
      (node (ref "U8") (pin "20") (pinfunction "(SCK/PCINT1)PB1_20") (pintype "bidirectional"))
    )
    (net (code "64") (name "SCL") (class "Default")
      (node (ref "Q13") (pin "3") (pinfunction "D_3") (pintype "passive"))
      (node (ref "R13") (pin "1") (pinfunction "1_1") (pintype "passive"))
      (node (ref "R19") (pin "2") (pinfunction "2_2") (pintype "passive"))
      (node (ref "R26") (pin "2") (pinfunction "2_2") (pintype "passive"))
      (node (ref "R36") (pin "1") (pinfunction "1_1") (pintype "passive"))
      (node (ref "R4") (pin "1") (pinfunction "1_1") (pintype "passive"))
      (node (ref "R8") (pin "1") (pinfunction "1_1") (pintype "passive"))
      (node (ref "SV18") (pin "3") (pinfunction "3_3") (pintype "passive"))
      (node (ref "SV18") (pin "4") (pinfunction "4_4") (pintype "passive"))
      (node (ref "SV19") (pin "3") (pinfunction "3_3") (pintype "passive"))
      (node (ref "SV19") (pin "4") (pinfunction "4_4") (pintype "passive"))
      (node (ref "SV5") (pin "3") (pinfunction "3_3") (pintype "passive"))
      (node (ref "SV5") (pin "4") (pinfunction "4_4") (pintype "passive"))
      (node (ref "U4") (pin "5") (pinfunction "SCL_5") (pintype "input"))
      (node (ref "U5") (pin "10") (pinfunction "SCL_10") (pintype "bidirectional"))
      (node (ref "U6") (pin "10") (pinfunction "SCL_10") (pintype "bidirectional"))
      (node (ref "U8") (pin "43") (pinfunction "(SCL/INT0)PD0_43") (pintype "bidirectional"))
    )
    (net (code "65") (name "SCL3") (class "Default")
      (node (ref "Q13") (pin "2") (pinfunction "S_2") (pintype "passive"))
      (node (ref "R5") (pin "1") (pinfunction "1_1") (pintype "passive"))
      (node (ref "SV13") (pin "3") (pinfunction "3_3") (pintype "passive"))
    )
    (net (code "66") (name "SDA") (class "Default")
      (node (ref "Q12") (pin "3") (pinfunction "D_3") (pintype "passive"))
      (node (ref "R12") (pin "1") (pinfunction "1_1") (pintype "passive"))
      (node (ref "R18") (pin "2") (pinfunction "2_2") (pintype "passive"))
      (node (ref "R2") (pin "1") (pinfunction "1_1") (pintype "passive"))
      (node (ref "R25") (pin "2") (pinfunction "2_2") (pintype "passive"))
      (node (ref "R35") (pin "1") (pinfunction "1_1") (pintype "passive"))
      (node (ref "R9") (pin "1") (pinfunction "1_1") (pintype "passive"))
      (node (ref "SV18") (pin "5") (pinfunction "5_5") (pintype "passive"))
      (node (ref "SV18") (pin "6") (pinfunction "6_6") (pintype "passive"))
      (node (ref "SV19") (pin "5") (pinfunction "5_5") (pintype "passive"))
      (node (ref "SV19") (pin "6") (pinfunction "6_6") (pintype "passive"))
      (node (ref "SV5") (pin "5") (pinfunction "5_5") (pintype "passive"))
      (node (ref "SV5") (pin "6") (pinfunction "6_6") (pintype "passive"))
      (node (ref "U4") (pin "6") (pinfunction "SDA_6") (pintype "bidirectional"))
      (node (ref "U5") (pin "9") (pinfunction "SDA_9") (pintype "bidirectional"))
      (node (ref "U6") (pin "9") (pinfunction "SDA_9") (pintype "bidirectional"))
      (node (ref "U8") (pin "44") (pinfunction "(SDA/INT1)PD1_44") (pintype "bidirectional"))
    )
    (net (code "67") (name "SDA3") (class "Default")
      (node (ref "Q12") (pin "2") (pinfunction "S_2") (pintype "passive"))
      (node (ref "R3") (pin "1") (pinfunction "1_1") (pintype "passive"))
      (node (ref "SV13") (pin "2") (pinfunction "2_2") (pintype "passive"))
    )
    (net (code "68") (name "SPEED") (class "Default")
      (node (ref "R1") (pin "2") (pinfunction "2_2") (pintype "passive"))
      (node (ref "U8") (pin "1") (pinfunction "(OC0B)PG5_1") (pintype "bidirectional"))
      (node (ref "X1") (pin "4") (pinfunction "KL_4") (pintype "passive"))
    )
    (net (code "69") (name "TX0") (class "Default")
      (node (ref "LED4") (pin "C") (pinfunction "C_C") (pintype "passive"))
      (node (ref "R14") (pin "2") (pinfunction "2_2") (pintype "passive"))
      (node (ref "SV1") (pin "2") (pinfunction "2_2") (pintype "passive"))
      (node (ref "U8") (pin "3") (pinfunction "(TXD0)PE1_3") (pintype "bidirectional"))
    )
    (net (code "70") (name "TXB") (class "Default")
      (node (ref "SV12") (pin "2") (pinfunction "2_2") (pintype "passive"))
      (node (ref "U8") (pin "64") (pinfunction "PJ1(TXD3/PCINT10)_64") (pintype "bidirectional"))
    )
    (net (code "71") (name "UD+") (class "Default")
      (node (ref "J2") (pin "3") (pinfunction "D+_3") (pintype "passive"))
      (node (ref "U$1") (pin "5") (pinfunction "UD+_5") (pintype "bidirectional"))
    )
    (net (code "72") (name "UD-") (class "Default")
      (node (ref "J2") (pin "2") (pinfunction "D-_2") (pintype "passive"))
      (node (ref "U$1") (pin "6") (pinfunction "UD-_6") (pintype "bidirectional"))
    )
    (net (code "73") (name "VBUS") (class "Default")
      (node (ref "D1") (pin "A") (pinfunction "A_A") (pintype "passive"))
      (node (ref "J2") (pin "1") (pinfunction "VBUS_1") (pintype "passive"))
    )
    (net (code "74") (name "VCC") (class "Default")
      (node (ref "F0") (pin "2") (pinfunction "2_2") (pintype "passive"))
      (node (ref "X2") (pin "2") (pinfunction "KL_2") (pintype "passive"))
    )
    (net (code "75") (name "VIN+") (class "Default")
      (node (ref "F0") (pin "1") (pinfunction "1_1") (pintype "passive"))
      (node (ref "R6") (pin "2") (pinfunction "2_2") (pintype "passive"))
      (node (ref "U4") (pin "1") (pinfunction "VIN+_1") (pintype "input"))
    )
    (net (code "76") (name "VIN-") (class "Default")
      (node (ref "R6") (pin "1") (pinfunction "1_1") (pintype "passive"))
      (node (ref "SV3") (pin "2") (pinfunction "2_2") (pintype "passive"))
      (node (ref "U4") (pin "2") (pinfunction "VIN-_2") (pintype "input"))
    )
    (net (code "77") (name "unconnected-(J2-ID-Pad4)") (class "Default")
      (node (ref "J2") (pin "4") (pinfunction "ID_4") (pintype "passive"))
    )
    (net (code "78") (name "unconnected-(U$1-CTS-Pad9)") (class "Default")
      (node (ref "U$1") (pin "9") (pinfunction "CTS_9") (pintype "bidirectional"))
    )
    (net (code "79") (name "unconnected-(U$1-DCD-Pad12)") (class "Default")
      (node (ref "U$1") (pin "12") (pinfunction "DCD_12") (pintype "bidirectional"))
    )
    (net (code "80") (name "unconnected-(U$1-DSR-Pad10)") (class "Default")
      (node (ref "U$1") (pin "10") (pinfunction "DSR_10") (pintype "bidirectional"))
    )
    (net (code "81") (name "unconnected-(U$1-R232-Pad15)") (class "Default")
      (node (ref "U$1") (pin "15") (pinfunction "R232_15") (pintype "bidirectional"))
    )
    (net (code "82") (name "unconnected-(U$1-RI-Pad11)") (class "Default")
      (node (ref "U$1") (pin "11") (pinfunction "RI_11") (pintype "bidirectional"))
    )
    (net (code "83") (name "unconnected-(U$1-RTS-Pad14)") (class "Default")
      (node (ref "U$1") (pin "14") (pinfunction "RTS_14") (pintype "bidirectional"))
    )
    (net (code "84") (name "unconnected-(U3-DIO2-Pad16)") (class "Default")
      (node (ref "U3") (pin "16") (pinfunction "DIO2_16") (pintype "bidirectional"))
    )
    (net (code "85") (name "unconnected-(U3-DIO3-Pad11)") (class "Default")
      (node (ref "U3") (pin "11") (pinfunction "DIO3_11") (pintype "bidirectional"))
    )
    (net (code "86") (name "unconnected-(U3-DIO4-Pad12)") (class "Default")
      (node (ref "U3") (pin "12") (pinfunction "DIO4_12") (pintype "bidirectional"))
    )
    (net (code "87") (name "unconnected-(U3-DIO5-Pad7)") (class "Default")
      (node (ref "U3") (pin "7") (pinfunction "DIO5_7") (pintype "bidirectional"))
    )
    (net (code "88") (name "unconnected-(U8-(A8)PC0-Pad53)") (class "Default")
      (node (ref "U8") (pin "53") (pinfunction "(A8)PC0_53") (pintype "bidirectional"))
    )
    (net (code "89") (name "unconnected-(U8-(A10)PC2-Pad55)") (class "Default")
      (node (ref "U8") (pin "55") (pinfunction "(A10)PC2_55") (pintype "bidirectional"))
    )
    (net (code "90") (name "unconnected-(U8-(A11)PC3-Pad56)") (class "Default")
      (node (ref "U8") (pin "56") (pinfunction "(A11)PC3_56") (pintype "bidirectional"))
    )
    (net (code "91") (name "unconnected-(U8-(A12)PC4-Pad57)") (class "Default")
      (node (ref "U8") (pin "57") (pinfunction "(A12)PC4_57") (pintype "bidirectional"))
    )
    (net (code "92") (name "unconnected-(U8-(A13)PC5-Pad58)") (class "Default")
      (node (ref "U8") (pin "58") (pinfunction "(A13)PC5_58") (pintype "bidirectional"))
    )
    (net (code "93") (name "unconnected-(U8-(A14)PC6-Pad59)") (class "Default")
      (node (ref "U8") (pin "59") (pinfunction "(A14)PC6_59") (pintype "bidirectional"))
    )
    (net (code "94") (name "unconnected-(U8-(A15)PC7-Pad60)") (class "Default")
      (node (ref "U8") (pin "60") (pinfunction "(A15)PC7_60") (pintype "bidirectional"))
    )
    (net (code "95") (name "unconnected-(U8-(AD0)PA0-Pad78)") (class "Default")
      (node (ref "U8") (pin "78") (pinfunction "(AD0)PA0_78") (pintype "bidirectional"))
    )
    (net (code "96") (name "unconnected-(U8-(AD1)PA1-Pad77)") (class "Default")
      (node (ref "U8") (pin "77") (pinfunction "(AD1)PA1_77") (pintype "bidirectional"))
    )
    (net (code "97") (name "unconnected-(U8-(AD2)PA2-Pad76)") (class "Default")
      (node (ref "U8") (pin "76") (pinfunction "(AD2)PA2_76") (pintype "bidirectional"))
    )
    (net (code "98") (name "unconnected-(U8-(AD3)PA3-Pad75)") (class "Default")
      (node (ref "U8") (pin "75") (pinfunction "(AD3)PA3_75") (pintype "bidirectional"))
    )
    (net (code "99") (name "unconnected-(U8-(AD4)PA4-Pad74)") (class "Default")
      (node (ref "U8") (pin "74") (pinfunction "(AD4)PA4_74") (pintype "bidirectional"))
    )
    (net (code "100") (name "unconnected-(U8-(AD5)PA5-Pad73)") (class "Default")
      (node (ref "U8") (pin "73") (pinfunction "(AD5)PA5_73") (pintype "bidirectional"))
    )
    (net (code "101") (name "unconnected-(U8-(AD6)PA6-Pad72)") (class "Default")
      (node (ref "U8") (pin "72") (pinfunction "(AD6)PA6_72") (pintype "bidirectional"))
    )
    (net (code "102") (name "unconnected-(U8-(AD7)PA7-Pad71)") (class "Default")
      (node (ref "U8") (pin "71") (pinfunction "(AD7)PA7_71") (pintype "bidirectional"))
    )
    (net (code "103") (name "unconnected-(U8-(ADC5{slash}TMS)PF5-Pad92)") (class "Default")
      (node (ref "U8") (pin "92") (pinfunction "(ADC5/TMS)PF5_92") (pintype "bidirectional"))
    )
    (net (code "104") (name "unconnected-(U8-(ADC6{slash}TDO)PF6-Pad91)") (class "Default")
      (node (ref "U8") (pin "91") (pinfunction "(ADC6/TDO)PF6_91") (pintype "bidirectional"))
    )
    (net (code "105") (name "unconnected-(U8-(ALE)PG2-Pad70)") (class "Default")
      (node (ref "U8") (pin "70") (pinfunction "(ALE)PG2_70") (pintype "bidirectional"))
    )
    (net (code "106") (name "unconnected-(U8-(CLKO{slash}ICP3{slash}INT7)PE7-Pad9)") (class "Default")
      (node (ref "U8") (pin "9") (pinfunction "(CLKO/ICP3/INT7)PE7_9") (pintype "bidirectional"))
    )
    (net (code "107") (name "unconnected-(U8-(ICP1)PD4-Pad47)") (class "Default")
      (node (ref "U8") (pin "47") (pinfunction "(ICP1)PD4_47") (pintype "bidirectional"))
    )
    (net (code "108") (name "unconnected-(U8-(RD)PG1-Pad52)") (class "Default")
      (node (ref "U8") (pin "52") (pinfunction "(RD)PG1_52") (pintype "bidirectional"))
    )
    (net (code "109") (name "unconnected-(U8-(T0)PD7-Pad50)") (class "Default")
      (node (ref "U8") (pin "50") (pinfunction "(T0)PD7_50") (pintype "bidirectional"))
    )
    (net (code "110") (name "unconnected-(U8-(T1)PD6-Pad49)") (class "Default")
      (node (ref "U8") (pin "49") (pinfunction "(T1)PD6_49") (pintype "bidirectional"))
    )
    (net (code "111") (name "unconnected-(U8-(T3{slash}INT6)PE6-Pad8)") (class "Default")
      (node (ref "U8") (pin "8") (pinfunction "(T3/INT6)PE6_8") (pintype "bidirectional"))
    )
    (net (code "112") (name "unconnected-(U8-(TOSC1)PG4-Pad29)") (class "Default")
      (node (ref "U8") (pin "29") (pinfunction "(TOSC1)PG4_29") (pintype "bidirectional"))
    )
    (net (code "113") (name "unconnected-(U8-(TOSC2)PG3-Pad28)") (class "Default")
      (node (ref "U8") (pin "28") (pinfunction "(TOSC2)PG3_28") (pintype "bidirectional"))
    )
    (net (code "114") (name "unconnected-(U8-(WR)PG0-Pad51)") (class "Default")
      (node (ref "U8") (pin "51") (pinfunction "(WR)PG0_51") (pintype "bidirectional"))
    )
    (net (code "115") (name "unconnected-(U8-(XCK1)PD5-Pad48)") (class "Default")
      (node (ref "U8") (pin "48") (pinfunction "(XCK1)PD5_48") (pintype "bidirectional"))
    )
    (net (code "116") (name "unconnected-(U8-PH0(RXD2)-Pad12)") (class "Default")
      (node (ref "U8") (pin "12") (pinfunction "PH0(RXD2)_12") (pintype "bidirectional"))
    )
    (net (code "117") (name "unconnected-(U8-PH1(TXD2)-Pad13)") (class "Default")
      (node (ref "U8") (pin "13") (pinfunction "PH1(TXD2)_13") (pintype "bidirectional"))
    )
    (net (code "118") (name "unconnected-(U8-PH2(XCK2)-Pad14)") (class "Default")
      (node (ref "U8") (pin "14") (pinfunction "PH2(XCK2)_14") (pintype "bidirectional"))
    )
    (net (code "119") (name "unconnected-(U8-PH3(OC4A)-Pad15)") (class "Default")
      (node (ref "U8") (pin "15") (pinfunction "PH3(OC4A)_15") (pintype "bidirectional"))
    )
    (net (code "120") (name "unconnected-(U8-PH4(OC4B)-Pad16)") (class "Default")
      (node (ref "U8") (pin "16") (pinfunction "PH4(OC4B)_16") (pintype "bidirectional"))
    )
    (net (code "121") (name "unconnected-(U8-PJ2(XCK3{slash}PCINT11)-Pad65)") (class "Default")
      (node (ref "U8") (pin "65") (pinfunction "PJ2(XCK3/PCINT11)_65") (pintype "bidirectional"))
    )
    (net (code "122") (name "unconnected-(U8-PJ3(PCINT12)-Pad66)") (class "Default")
      (node (ref "U8") (pin "66") (pinfunction "PJ3(PCINT12)_66") (pintype "bidirectional"))
    )
    (net (code "123") (name "unconnected-(U8-PJ4(PCINT13)-Pad67)") (class "Default")
      (node (ref "U8") (pin "67") (pinfunction "PJ4(PCINT13)_67") (pintype "bidirectional"))
    )
    (net (code "124") (name "unconnected-(U8-PJ5(PCINT14)-Pad68)") (class "Default")
      (node (ref "U8") (pin "68") (pinfunction "PJ5(PCINT14)_68") (pintype "bidirectional"))
    )
    (net (code "125") (name "unconnected-(U8-PJ6(PCINT15)-Pad69)") (class "Default")
      (node (ref "U8") (pin "69") (pinfunction "PJ6(PCINT15)_69") (pintype "bidirectional"))
    )
    (net (code "126") (name "unconnected-(U8-PJ7-Pad79)") (class "Default")
      (node (ref "U8") (pin "79") (pinfunction "PJ7_79") (pintype "bidirectional"))
    )
    (net (code "127") (name "unconnected-(U8-PK1(ADC9{slash}PCINT17)-Pad88)") (class "Default")
      (node (ref "U8") (pin "88") (pinfunction "PK1(ADC9/PCINT17)_88") (pintype "bidirectional"))
    )
    (net (code "128") (name "unconnected-(U8-PK2(ADC10{slash}PCINT18)-Pad87)") (class "Default")
      (node (ref "U8") (pin "87") (pinfunction "PK2(ADC10/PCINT18)_87") (pintype "bidirectional"))
    )
    (net (code "129") (name "unconnected-(U8-PK3(ADC11{slash}PCINT19)-Pad86)") (class "Default")
      (node (ref "U8") (pin "86") (pinfunction "PK3(ADC11/PCINT19)_86") (pintype "bidirectional"))
    )
    (net (code "130") (name "unconnected-(U8-PK4(ADC12{slash}PCINT20)-Pad85)") (class "Default")
      (node (ref "U8") (pin "85") (pinfunction "PK4(ADC12/PCINT20)_85") (pintype "bidirectional"))
    )
    (net (code "131") (name "unconnected-(U8-PK5(ADC13{slash}PCINT21)-Pad84)") (class "Default")
      (node (ref "U8") (pin "84") (pinfunction "PK5(ADC13/PCINT21)_84") (pintype "bidirectional"))
    )
    (net (code "132") (name "unconnected-(U8-PK6(ADC14{slash}PCINT22)-Pad83)") (class "Default")
      (node (ref "U8") (pin "83") (pinfunction "PK6(ADC14/PCINT22)_83") (pintype "bidirectional"))
    )
    (net (code "133") (name "unconnected-(U8-PK7(ADC15{slash}PCINT23)-Pad82)") (class "Default")
      (node (ref "U8") (pin "82") (pinfunction "PK7(ADC15/PCINT23)_82") (pintype "bidirectional"))
    )
    (net (code "134") (name "unconnected-(U8-PL0(ICP4)-Pad35)") (class "Default")
      (node (ref "U8") (pin "35") (pinfunction "PL0(ICP4)_35") (pintype "bidirectional"))
    )
    (net (code "135") (name "unconnected-(U8-PL1(ICP5)-Pad36)") (class "Default")
      (node (ref "U8") (pin "36") (pinfunction "PL1(ICP5)_36") (pintype "bidirectional"))
    )
    (net (code "136") (name "unconnected-(U8-PL2(T5)-Pad37)") (class "Default")
      (node (ref "U8") (pin "37") (pinfunction "PL2(T5)_37") (pintype "bidirectional"))
    )
    (net (code "137") (name "unconnected-(U8-PL3(OC5A)-Pad38)") (class "Default")
      (node (ref "U8") (pin "38") (pinfunction "PL3(OC5A)_38") (pintype "bidirectional"))
    )
    (net (code "138") (name "unconnected-(U8-PL4(OC5B)-Pad39)") (class "Default")
      (node (ref "U8") (pin "39") (pinfunction "PL4(OC5B)_39") (pintype "bidirectional"))
    )
    (net (code "139") (name "unconnected-(U8-PL5(OC5C)-Pad40)") (class "Default")
      (node (ref "U8") (pin "40") (pinfunction "PL5(OC5C)_40") (pintype "bidirectional"))
    )
    (net (code "140") (name "unconnected-(U8-PL6-Pad41)") (class "Default")
      (node (ref "U8") (pin "41") (pinfunction "PL6_41") (pintype "bidirectional"))
    )
    (net (code "141") (name "unconnected-(U8-PL7-Pad42)") (class "Default")
      (node (ref "U8") (pin "42") (pinfunction "PL7_42") (pintype "bidirectional"))
    )
  )
)
